# untitled.net
KiCad netlist of a schematic drawn in EAGLE
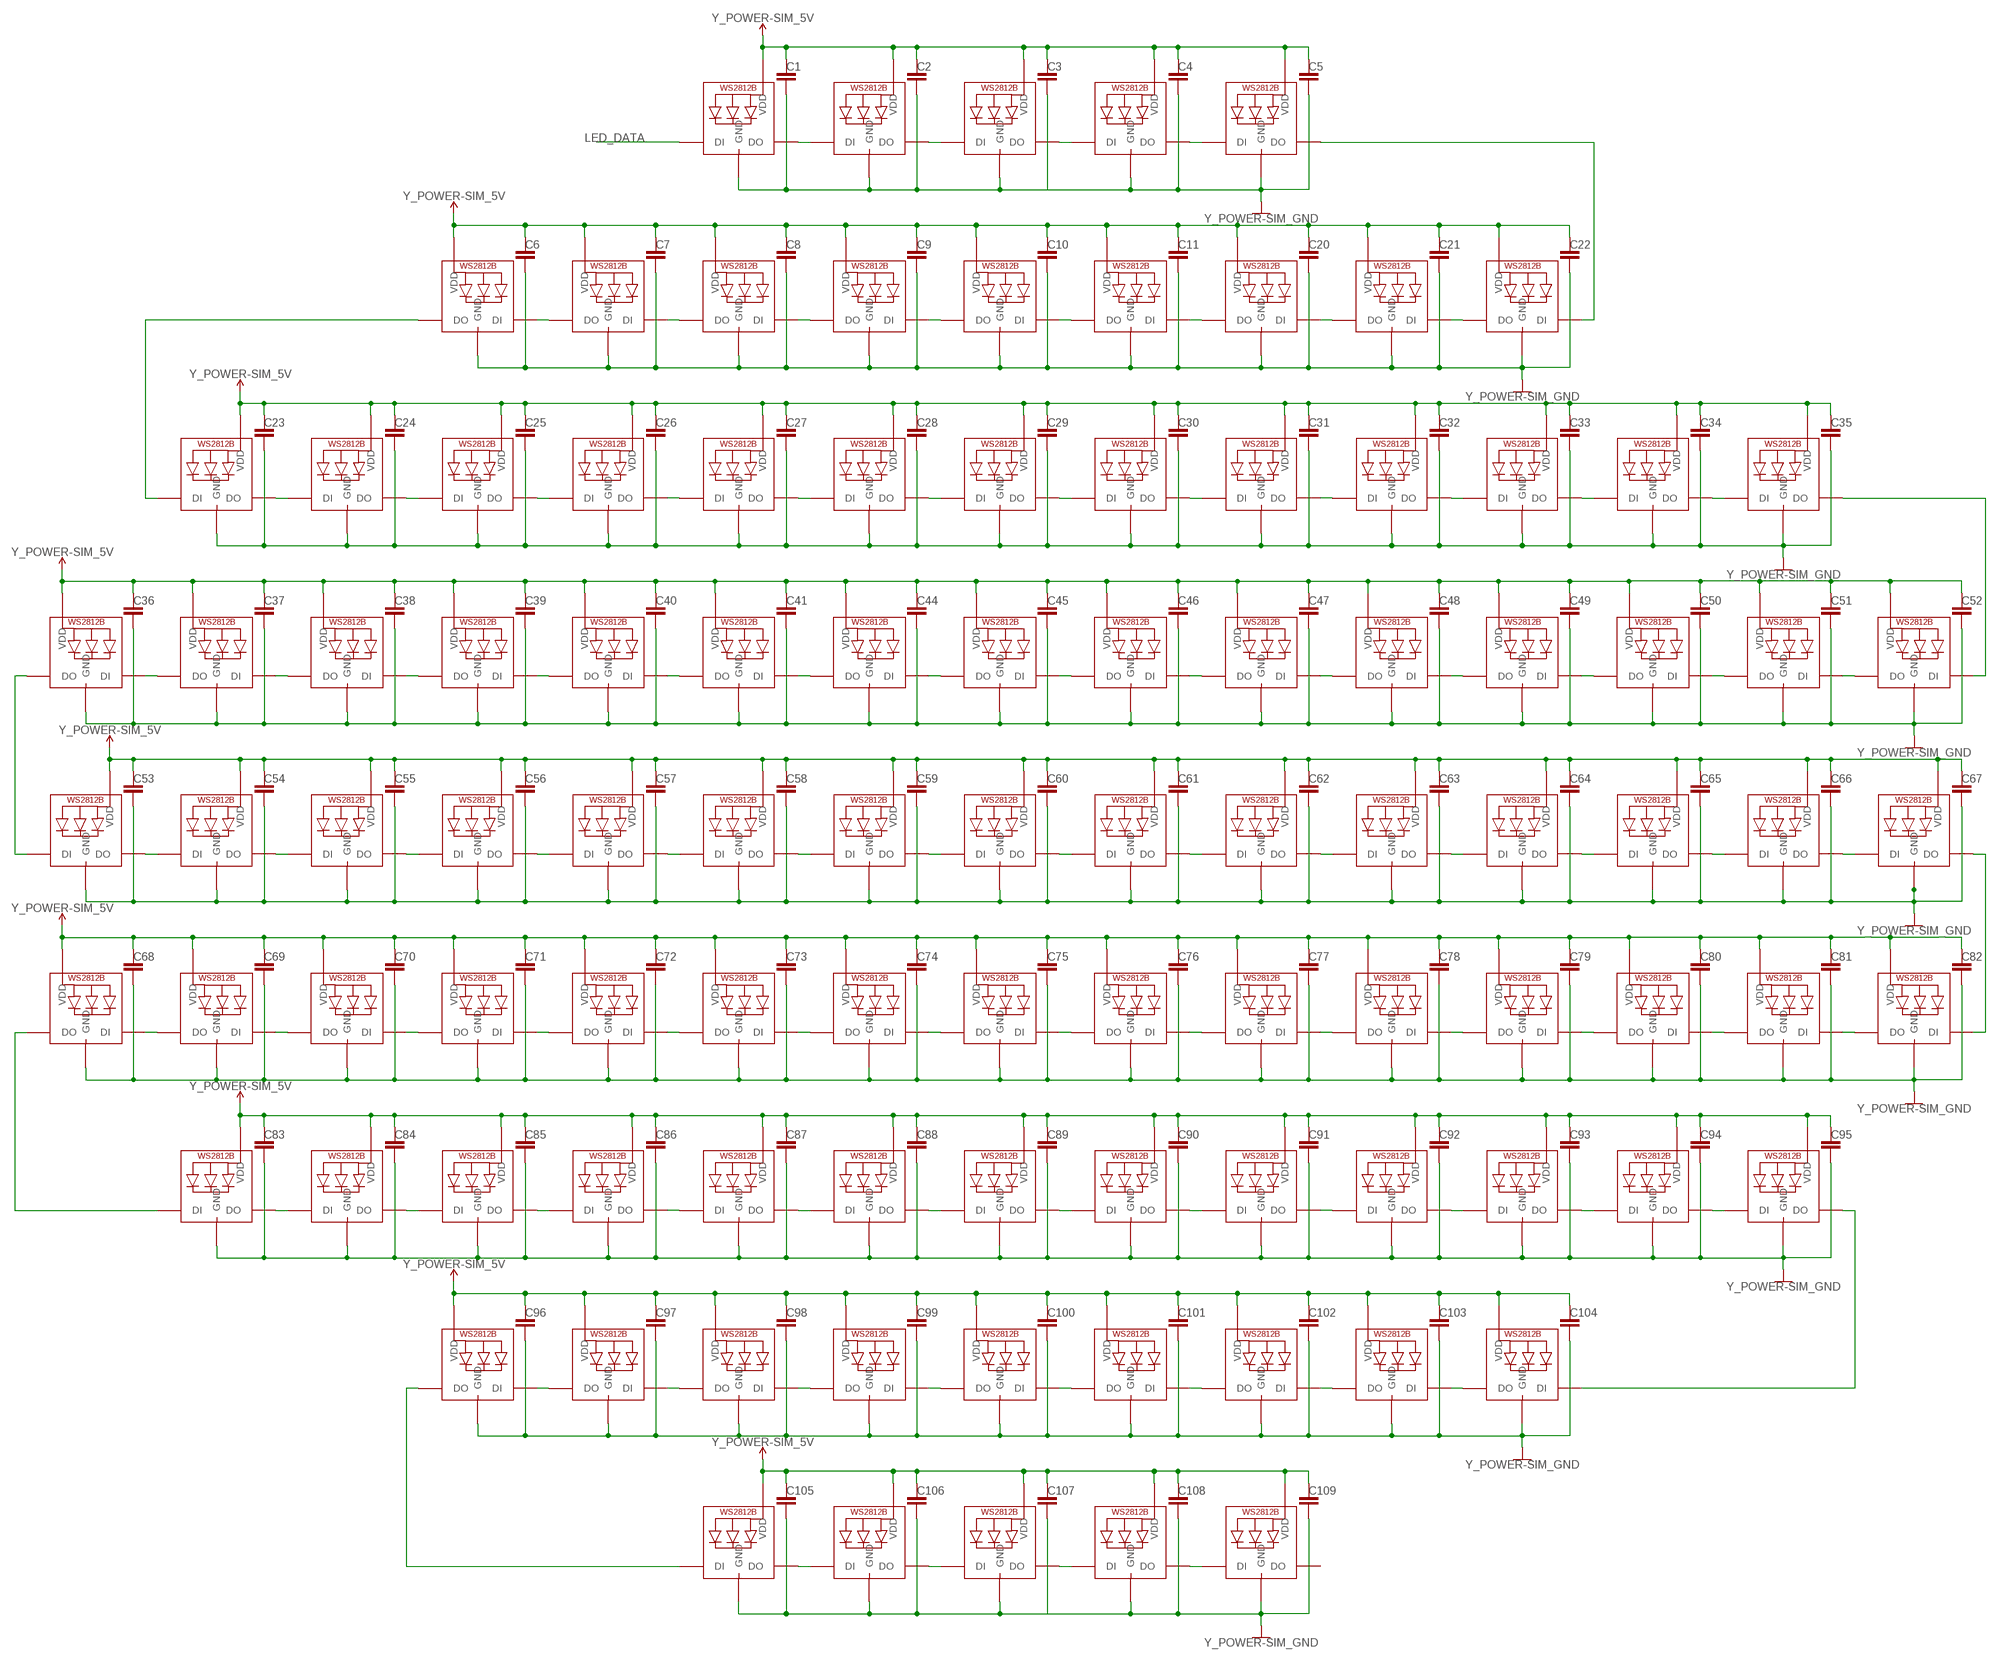
[diagram p0: schematic, sheet 1, part 1 of 2]
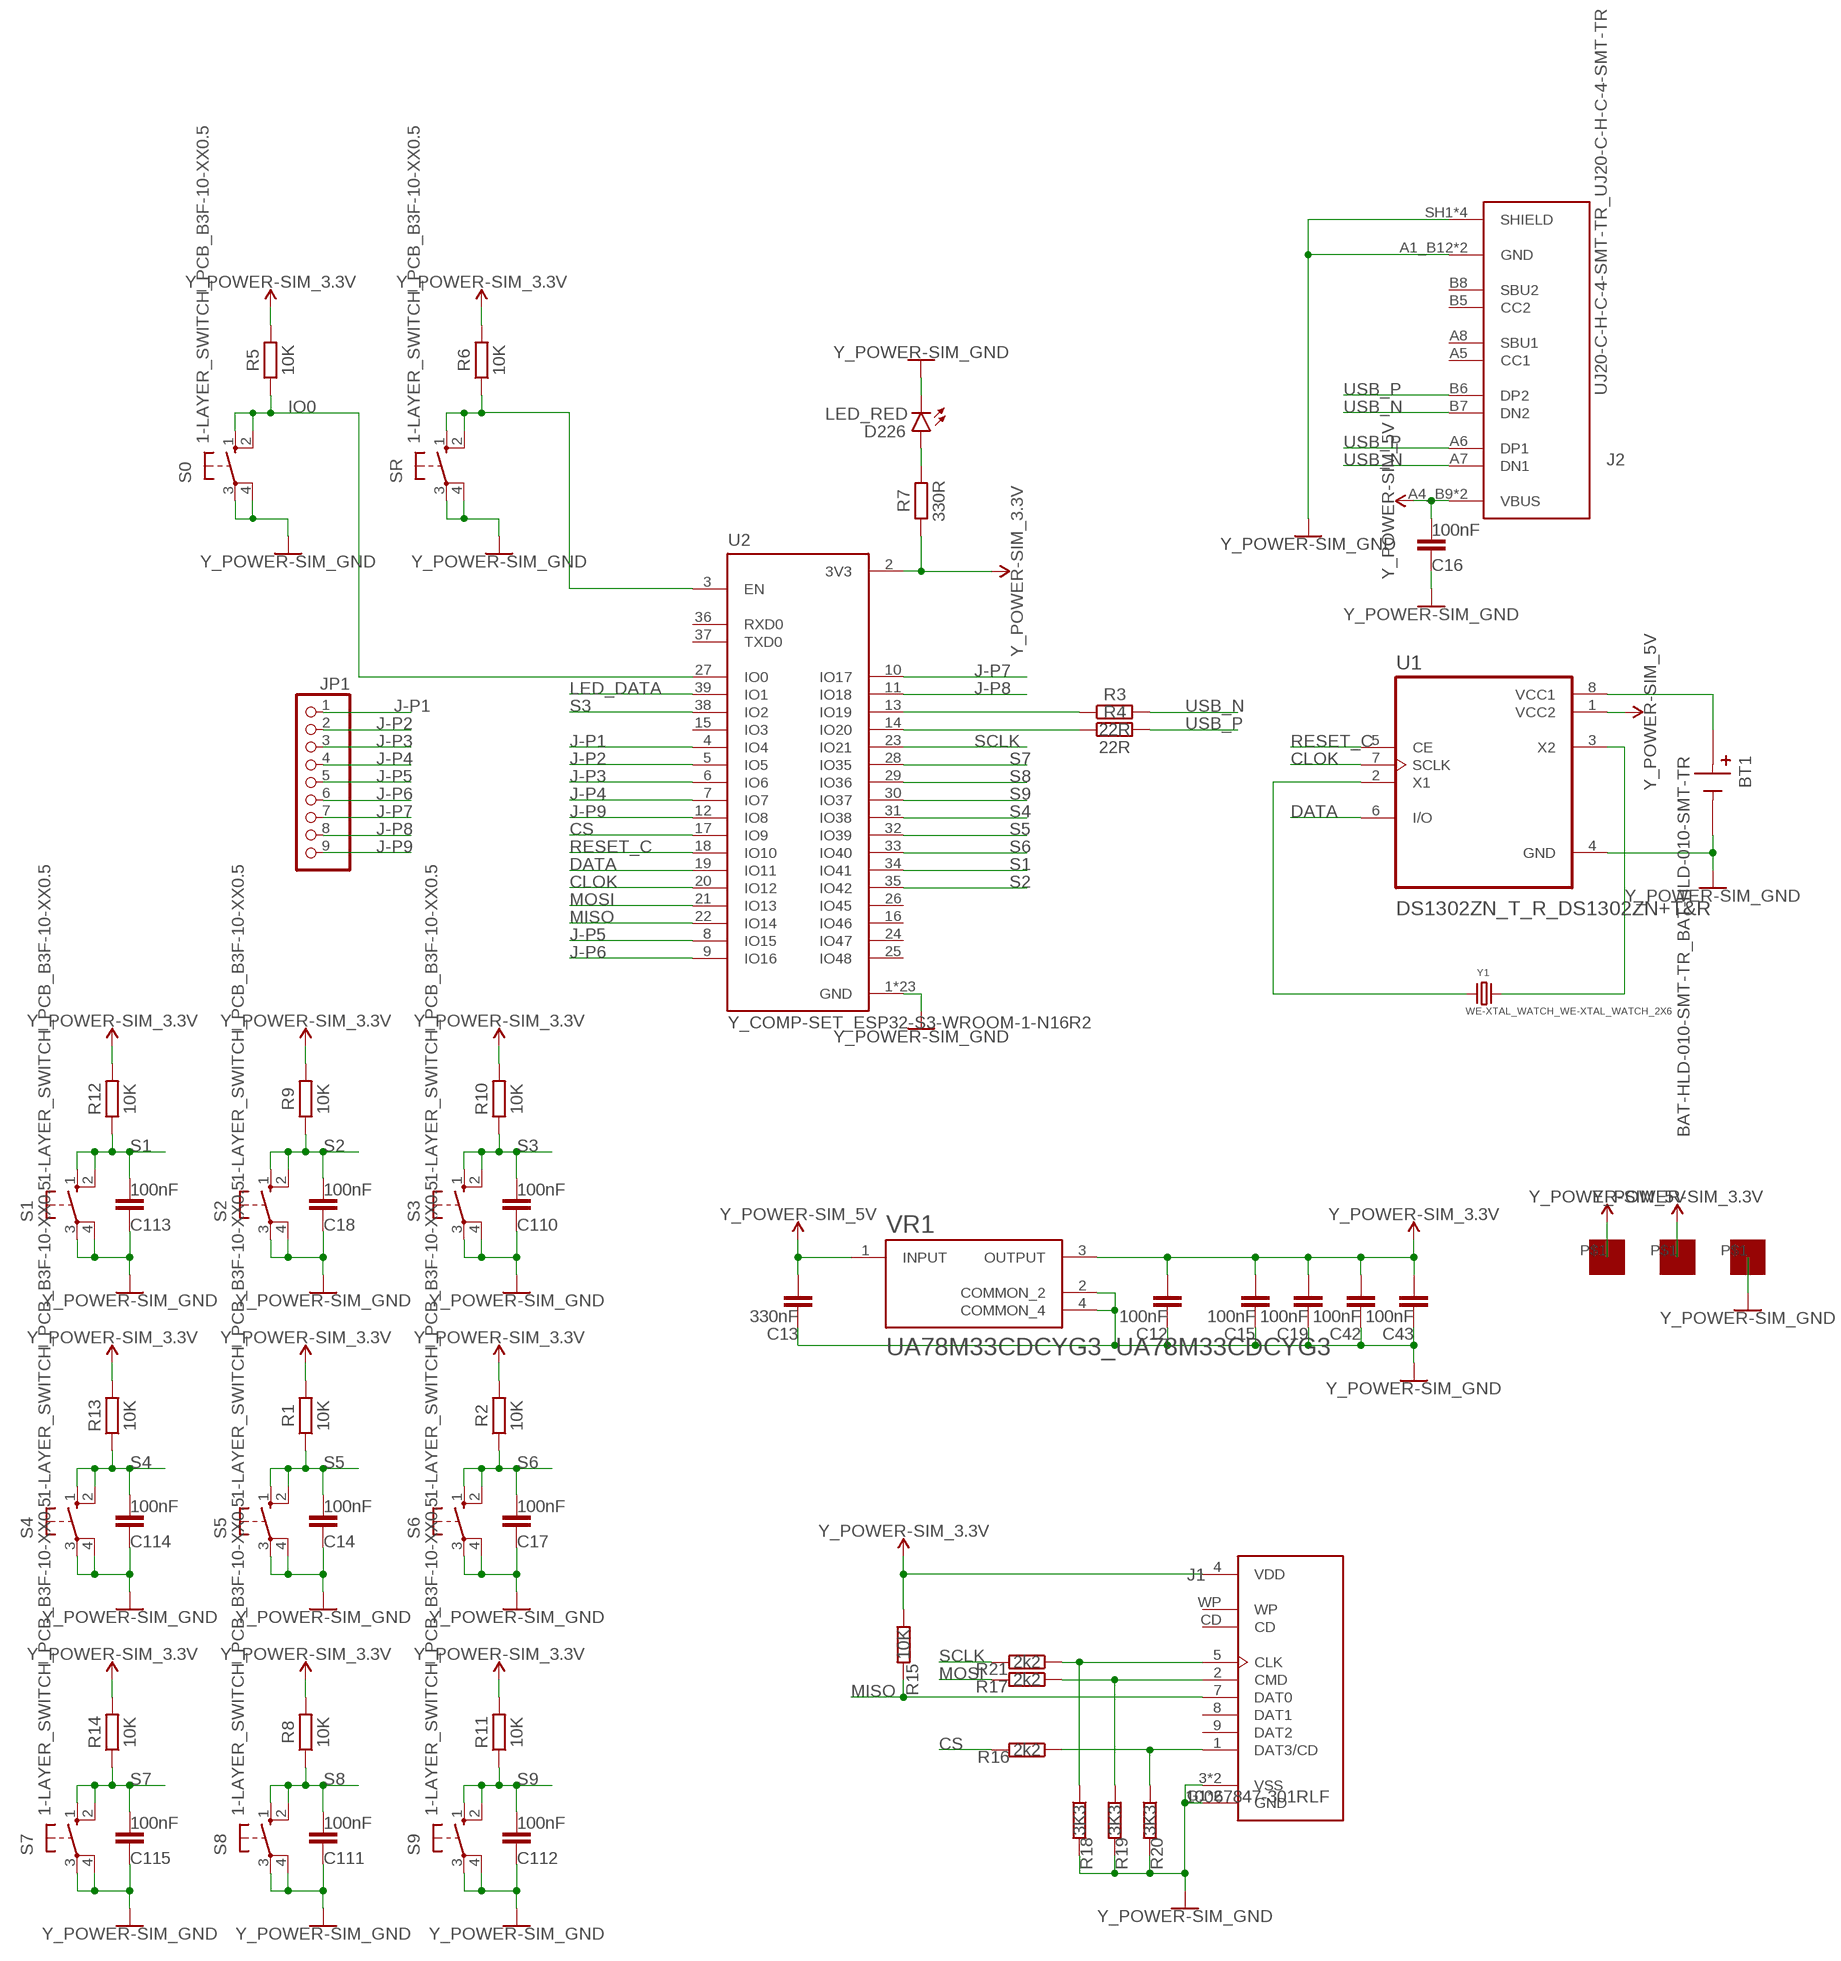
[diagram p1: schematic, sheet 1, part 2 of 2]

(export (version "E")
  (design (tool "Eeschema 10.0.6"))
  (components
    (comp (ref "BT1")
      (value "BAT-HLD-010-SMT-TR_BAT-HLD-010-SMT-TR")
      (footprint "eagle-import:BAT-HLD-010-SMT-TR_BAT_BAT-HLD-010-SMT-TR")
      (fields (field (name "MF") "TE Connectivity") (field (name "MP") "BAT-HLD-010-SMT-TR"))
      (libsource (lib "eagle-import") (part "BAT-HLD-010-SMT-TR_BAT-HLD-010-SMT-TR"))
    )
    (comp (ref "C1")
      (value "Y-CAP_C_CHIP-0805(2012-METRIC)")
      (footprint "eagle-import:Y-CAP_CAPC2012X110")
      (libsource (lib "eagle-import") (part "Y-CAP_CCHIP-0805(2012-METRIC)_"))
    )
    (comp (ref "C2")
      (value "Y-CAP_C_CHIP-0805(2012-METRIC)")
      (footprint "eagle-import:Y-CAP_CAPC2012X110")
      (libsource (lib "eagle-import") (part "Y-CAP_CCHIP-0805(2012-METRIC)_"))
    )
    (comp (ref "C3")
      (value "Y-CAP_C_CHIP-0805(2012-METRIC)")
      (footprint "eagle-import:Y-CAP_CAPC2012X110")
      (libsource (lib "eagle-import") (part "Y-CAP_CCHIP-0805(2012-METRIC)_"))
    )
    (comp (ref "C4")
      (value "Y-CAP_C_CHIP-0805(2012-METRIC)")
      (footprint "eagle-import:Y-CAP_CAPC2012X110")
      (libsource (lib "eagle-import") (part "Y-CAP_CCHIP-0805(2012-METRIC)_"))
    )
    (comp (ref "C5")
      (value "Y-CAP_C_CHIP-0805(2012-METRIC)")
      (footprint "eagle-import:Y-CAP_CAPC2012X110")
      (libsource (lib "eagle-import") (part "Y-CAP_CCHIP-0805(2012-METRIC)_"))
    )
    (comp (ref "C6")
      (value "Y-CAP_C_CHIP-0805(2012-METRIC)")
      (footprint "eagle-import:Y-CAP_CAPC2012X110")
      (libsource (lib "eagle-import") (part "Y-CAP_CCHIP-0805(2012-METRIC)_"))
    )
    (comp (ref "C7")
      (value "Y-CAP_C_CHIP-0805(2012-METRIC)")
      (footprint "eagle-import:Y-CAP_CAPC2012X110")
      (libsource (lib "eagle-import") (part "Y-CAP_CCHIP-0805(2012-METRIC)_"))
    )
    (comp (ref "C8")
      (value "Y-CAP_C_CHIP-0805(2012-METRIC)")
      (footprint "eagle-import:Y-CAP_CAPC2012X110")
      (libsource (lib "eagle-import") (part "Y-CAP_CCHIP-0805(2012-METRIC)_"))
    )
    (comp (ref "C9")
      (value "Y-CAP_C_CHIP-0805(2012-METRIC)")
      (footprint "eagle-import:Y-CAP_CAPC2012X110")
      (libsource (lib "eagle-import") (part "Y-CAP_CCHIP-0805(2012-METRIC)_"))
    )
    (comp (ref "C10")
      (value "Y-CAP_C_CHIP-0805(2012-METRIC)")
      (footprint "eagle-import:Y-CAP_CAPC2012X110")
      (libsource (lib "eagle-import") (part "Y-CAP_CCHIP-0805(2012-METRIC)_"))
    )
    (comp (ref "C11")
      (value "Y-CAP_C_CHIP-0805(2012-METRIC)")
      (footprint "eagle-import:Y-CAP_CAPC2012X110")
      (libsource (lib "eagle-import") (part "Y-CAP_CCHIP-0805(2012-METRIC)_"))
    )
    (comp (ref "C12")
      (value "100nF")
      (footprint "eagle-import:Y-CAP_CAPC2012X110")
      (libsource (lib "eagle-import") (part "Y-CAP_CCHIP-0805(2012-METRIC)_"))
    )
    (comp (ref "C13")
      (value "330nF")
      (footprint "eagle-import:Y-CAP_CAPC2012X110")
      (libsource (lib "eagle-import") (part "Y-CAP_CCHIP-0805(2012-METRIC)_"))
    )
    (comp (ref "C14")
      (value "100nF")
      (footprint "eagle-import:Y-CAP_CAPC2012X110")
      (libsource (lib "eagle-import") (part "Y-CAP_CCHIP-0805(2012-METRIC)_"))
    )
    (comp (ref "C15")
      (value "100nF")
      (footprint "eagle-import:Y-CAP_CAPC2012X110")
      (libsource (lib "eagle-import") (part "Y-CAP_CCHIP-0805(2012-METRIC)_"))
    )
    (comp (ref "C16")
      (value "100nF")
      (footprint "eagle-import:Y-CAP_CAPC2012X110")
      (libsource (lib "eagle-import") (part "Y-CAP_CCHIP-0805(2012-METRIC)_"))
    )
    (comp (ref "C17")
      (value "100nF")
      (footprint "eagle-import:Y-CAP_CAPC2012X110")
      (libsource (lib "eagle-import") (part "Y-CAP_CCHIP-0805(2012-METRIC)_"))
    )
    (comp (ref "C18")
      (value "100nF")
      (footprint "eagle-import:Y-CAP_CAPC2012X110")
      (libsource (lib "eagle-import") (part "Y-CAP_CCHIP-0805(2012-METRIC)_"))
    )
    (comp (ref "C19")
      (value "100nF")
      (footprint "eagle-import:Y-CAP_CAPC2012X110")
      (libsource (lib "eagle-import") (part "Y-CAP_CCHIP-0805(2012-METRIC)_"))
    )
    (comp (ref "C20")
      (value "Y-CAP_C_CHIP-0805(2012-METRIC)")
      (footprint "eagle-import:Y-CAP_CAPC2012X110")
      (libsource (lib "eagle-import") (part "Y-CAP_CCHIP-0805(2012-METRIC)_"))
    )
    (comp (ref "C21")
      (value "Y-CAP_C_CHIP-0805(2012-METRIC)")
      (footprint "eagle-import:Y-CAP_CAPC2012X110")
      (libsource (lib "eagle-import") (part "Y-CAP_CCHIP-0805(2012-METRIC)_"))
    )
    (comp (ref "C22")
      (value "Y-CAP_C_CHIP-0805(2012-METRIC)")
      (footprint "eagle-import:Y-CAP_CAPC2012X110")
      (libsource (lib "eagle-import") (part "Y-CAP_CCHIP-0805(2012-METRIC)_"))
    )
    (comp (ref "C23")
      (value "Y-CAP_C_CHIP-0805(2012-METRIC)")
      (footprint "eagle-import:Y-CAP_CAPC2012X110")
      (libsource (lib "eagle-import") (part "Y-CAP_CCHIP-0805(2012-METRIC)_"))
    )
    (comp (ref "C24")
      (value "Y-CAP_C_CHIP-0805(2012-METRIC)")
      (footprint "eagle-import:Y-CAP_CAPC2012X110")
      (libsource (lib "eagle-import") (part "Y-CAP_CCHIP-0805(2012-METRIC)_"))
    )
    (comp (ref "C25")
      (value "Y-CAP_C_CHIP-0805(2012-METRIC)")
      (footprint "eagle-import:Y-CAP_CAPC2012X110")
      (libsource (lib "eagle-import") (part "Y-CAP_CCHIP-0805(2012-METRIC)_"))
    )
    (comp (ref "C26")
      (value "Y-CAP_C_CHIP-0805(2012-METRIC)")
      (footprint "eagle-import:Y-CAP_CAPC2012X110")
      (libsource (lib "eagle-import") (part "Y-CAP_CCHIP-0805(2012-METRIC)_"))
    )
    (comp (ref "C27")
      (value "Y-CAP_C_CHIP-0805(2012-METRIC)")
      (footprint "eagle-import:Y-CAP_CAPC2012X110")
      (libsource (lib "eagle-import") (part "Y-CAP_CCHIP-0805(2012-METRIC)_"))
    )
    (comp (ref "C28")
      (value "Y-CAP_C_CHIP-0805(2012-METRIC)")
      (footprint "eagle-import:Y-CAP_CAPC2012X110")
      (libsource (lib "eagle-import") (part "Y-CAP_CCHIP-0805(2012-METRIC)_"))
    )
    (comp (ref "C29")
      (value "Y-CAP_C_CHIP-0805(2012-METRIC)")
      (footprint "eagle-import:Y-CAP_CAPC2012X110")
      (libsource (lib "eagle-import") (part "Y-CAP_CCHIP-0805(2012-METRIC)_"))
    )
    (comp (ref "C30")
      (value "Y-CAP_C_CHIP-0805(2012-METRIC)")
      (footprint "eagle-import:Y-CAP_CAPC2012X110")
      (libsource (lib "eagle-import") (part "Y-CAP_CCHIP-0805(2012-METRIC)_"))
    )
    (comp (ref "C31")
      (value "Y-CAP_C_CHIP-0805(2012-METRIC)")
      (footprint "eagle-import:Y-CAP_CAPC2012X110")
      (libsource (lib "eagle-import") (part "Y-CAP_CCHIP-0805(2012-METRIC)_"))
    )
    (comp (ref "C32")
      (value "Y-CAP_C_CHIP-0805(2012-METRIC)")
      (footprint "eagle-import:Y-CAP_CAPC2012X110")
      (libsource (lib "eagle-import") (part "Y-CAP_CCHIP-0805(2012-METRIC)_"))
    )
    (comp (ref "C33")
      (value "Y-CAP_C_CHIP-0805(2012-METRIC)")
      (footprint "eagle-import:Y-CAP_CAPC2012X110")
      (libsource (lib "eagle-import") (part "Y-CAP_CCHIP-0805(2012-METRIC)_"))
    )
    (comp (ref "C34")
      (value "Y-CAP_C_CHIP-0805(2012-METRIC)")
      (footprint "eagle-import:Y-CAP_CAPC2012X110")
      (libsource (lib "eagle-import") (part "Y-CAP_CCHIP-0805(2012-METRIC)_"))
    )
    (comp (ref "C35")
      (value "Y-CAP_C_CHIP-0805(2012-METRIC)")
      (footprint "eagle-import:Y-CAP_CAPC2012X110")
      (libsource (lib "eagle-import") (part "Y-CAP_CCHIP-0805(2012-METRIC)_"))
    )
    (comp (ref "C36")
      (value "Y-CAP_C_CHIP-0805(2012-METRIC)")
      (footprint "eagle-import:Y-CAP_CAPC2012X110")
      (libsource (lib "eagle-import") (part "Y-CAP_CCHIP-0805(2012-METRIC)_"))
    )
    (comp (ref "C37")
      (value "Y-CAP_C_CHIP-0805(2012-METRIC)")
      (footprint "eagle-import:Y-CAP_CAPC2012X110")
      (libsource (lib "eagle-import") (part "Y-CAP_CCHIP-0805(2012-METRIC)_"))
    )
    (comp (ref "C38")
      (value "Y-CAP_C_CHIP-0805(2012-METRIC)")
      (footprint "eagle-import:Y-CAP_CAPC2012X110")
      (libsource (lib "eagle-import") (part "Y-CAP_CCHIP-0805(2012-METRIC)_"))
    )
    (comp (ref "C39")
      (value "Y-CAP_C_CHIP-0805(2012-METRIC)")
      (footprint "eagle-import:Y-CAP_CAPC2012X110")
      (libsource (lib "eagle-import") (part "Y-CAP_CCHIP-0805(2012-METRIC)_"))
    )
    (comp (ref "C40")
      (value "Y-CAP_C_CHIP-0805(2012-METRIC)")
      (footprint "eagle-import:Y-CAP_CAPC2012X110")
      (libsource (lib "eagle-import") (part "Y-CAP_CCHIP-0805(2012-METRIC)_"))
    )
    (comp (ref "C41")
      (value "Y-CAP_C_CHIP-0805(2012-METRIC)")
      (footprint "eagle-import:Y-CAP_CAPC2012X110")
      (libsource (lib "eagle-import") (part "Y-CAP_CCHIP-0805(2012-METRIC)_"))
    )
    (comp (ref "C42")
      (value "100nF")
      (footprint "eagle-import:Y-CAP_CAPC2012X110")
      (libsource (lib "eagle-import") (part "Y-CAP_CCHIP-0805(2012-METRIC)_"))
    )
    (comp (ref "C43")
      (value "100nF")
      (footprint "eagle-import:Y-CAP_CAPC2012X110")
      (libsource (lib "eagle-import") (part "Y-CAP_CCHIP-0805(2012-METRIC)_"))
    )
    (comp (ref "C44")
      (value "Y-CAP_C_CHIP-0805(2012-METRIC)")
      (footprint "eagle-import:Y-CAP_CAPC2012X110")
      (libsource (lib "eagle-import") (part "Y-CAP_CCHIP-0805(2012-METRIC)_"))
    )
    (comp (ref "C45")
      (value "Y-CAP_C_CHIP-0805(2012-METRIC)")
      (footprint "eagle-import:Y-CAP_CAPC2012X110")
      (libsource (lib "eagle-import") (part "Y-CAP_CCHIP-0805(2012-METRIC)_"))
    )
    (comp (ref "C46")
      (value "Y-CAP_C_CHIP-0805(2012-METRIC)")
      (footprint "eagle-import:Y-CAP_CAPC2012X110")
      (libsource (lib "eagle-import") (part "Y-CAP_CCHIP-0805(2012-METRIC)_"))
    )
    (comp (ref "C47")
      (value "Y-CAP_C_CHIP-0805(2012-METRIC)")
      (footprint "eagle-import:Y-CAP_CAPC2012X110")
      (libsource (lib "eagle-import") (part "Y-CAP_CCHIP-0805(2012-METRIC)_"))
    )
    (comp (ref "C48")
      (value "Y-CAP_C_CHIP-0805(2012-METRIC)")
      (footprint "eagle-import:Y-CAP_CAPC2012X110")
      (libsource (lib "eagle-import") (part "Y-CAP_CCHIP-0805(2012-METRIC)_"))
    )
    (comp (ref "C49")
      (value "Y-CAP_C_CHIP-0805(2012-METRIC)")
      (footprint "eagle-import:Y-CAP_CAPC2012X110")
      (libsource (lib "eagle-import") (part "Y-CAP_CCHIP-0805(2012-METRIC)_"))
    )
    (comp (ref "C50")
      (value "Y-CAP_C_CHIP-0805(2012-METRIC)")
      (footprint "eagle-import:Y-CAP_CAPC2012X110")
      (libsource (lib "eagle-import") (part "Y-CAP_CCHIP-0805(2012-METRIC)_"))
    )
    (comp (ref "C51")
      (value "Y-CAP_C_CHIP-0805(2012-METRIC)")
      (footprint "eagle-import:Y-CAP_CAPC2012X110")
      (libsource (lib "eagle-import") (part "Y-CAP_CCHIP-0805(2012-METRIC)_"))
    )
    (comp (ref "C52")
      (value "Y-CAP_C_CHIP-0805(2012-METRIC)")
      (footprint "eagle-import:Y-CAP_CAPC2012X110")
      (libsource (lib "eagle-import") (part "Y-CAP_CCHIP-0805(2012-METRIC)_"))
    )
    (comp (ref "C53")
      (value "Y-CAP_C_CHIP-0805(2012-METRIC)")
      (footprint "eagle-import:Y-CAP_CAPC2012X110")
      (libsource (lib "eagle-import") (part "Y-CAP_CCHIP-0805(2012-METRIC)_"))
    )
    (comp (ref "C54")
      (value "Y-CAP_C_CHIP-0805(2012-METRIC)")
      (footprint "eagle-import:Y-CAP_CAPC2012X110")
      (libsource (lib "eagle-import") (part "Y-CAP_CCHIP-0805(2012-METRIC)_"))
    )
    (comp (ref "C55")
      (value "Y-CAP_C_CHIP-0805(2012-METRIC)")
      (footprint "eagle-import:Y-CAP_CAPC2012X110")
      (libsource (lib "eagle-import") (part "Y-CAP_CCHIP-0805(2012-METRIC)_"))
    )
    (comp (ref "C56")
      (value "Y-CAP_C_CHIP-0805(2012-METRIC)")
      (footprint "eagle-import:Y-CAP_CAPC2012X110")
      (libsource (lib "eagle-import") (part "Y-CAP_CCHIP-0805(2012-METRIC)_"))
    )
    (comp (ref "C57")
      (value "Y-CAP_C_CHIP-0805(2012-METRIC)")
      (footprint "eagle-import:Y-CAP_CAPC2012X110")
      (libsource (lib "eagle-import") (part "Y-CAP_CCHIP-0805(2012-METRIC)_"))
    )
    (comp (ref "C58")
      (value "Y-CAP_C_CHIP-0805(2012-METRIC)")
      (footprint "eagle-import:Y-CAP_CAPC2012X110")
      (libsource (lib "eagle-import") (part "Y-CAP_CCHIP-0805(2012-METRIC)_"))
    )
    (comp (ref "C59")
      (value "Y-CAP_C_CHIP-0805(2012-METRIC)")
      (footprint "eagle-import:Y-CAP_CAPC2012X110")
      (libsource (lib "eagle-import") (part "Y-CAP_CCHIP-0805(2012-METRIC)_"))
    )
    (comp (ref "C60")
      (value "Y-CAP_C_CHIP-0805(2012-METRIC)")
      (footprint "eagle-import:Y-CAP_CAPC2012X110")
      (libsource (lib "eagle-import") (part "Y-CAP_CCHIP-0805(2012-METRIC)_"))
    )
    (comp (ref "C61")
      (value "Y-CAP_C_CHIP-0805(2012-METRIC)")
      (footprint "eagle-import:Y-CAP_CAPC2012X110")
      (libsource (lib "eagle-import") (part "Y-CAP_CCHIP-0805(2012-METRIC)_"))
    )
    (comp (ref "C62")
      (value "Y-CAP_C_CHIP-0805(2012-METRIC)")
      (footprint "eagle-import:Y-CAP_CAPC2012X110")
      (libsource (lib "eagle-import") (part "Y-CAP_CCHIP-0805(2012-METRIC)_"))
    )
    (comp (ref "C63")
      (value "Y-CAP_C_CHIP-0805(2012-METRIC)")
      (footprint "eagle-import:Y-CAP_CAPC2012X110")
      (libsource (lib "eagle-import") (part "Y-CAP_CCHIP-0805(2012-METRIC)_"))
    )
    (comp (ref "C64")
      (value "Y-CAP_C_CHIP-0805(2012-METRIC)")
      (footprint "eagle-import:Y-CAP_CAPC2012X110")
      (libsource (lib "eagle-import") (part "Y-CAP_CCHIP-0805(2012-METRIC)_"))
    )
    (comp (ref "C65")
      (value "Y-CAP_C_CHIP-0805(2012-METRIC)")
      (footprint "eagle-import:Y-CAP_CAPC2012X110")
      (libsource (lib "eagle-import") (part "Y-CAP_CCHIP-0805(2012-METRIC)_"))
    )
    (comp (ref "C66")
      (value "Y-CAP_C_CHIP-0805(2012-METRIC)")
      (footprint "eagle-import:Y-CAP_CAPC2012X110")
      (libsource (lib "eagle-import") (part "Y-CAP_CCHIP-0805(2012-METRIC)_"))
    )
    (comp (ref "C67")
      (value "Y-CAP_C_CHIP-0805(2012-METRIC)")
      (footprint "eagle-import:Y-CAP_CAPC2012X110")
      (libsource (lib "eagle-import") (part "Y-CAP_CCHIP-0805(2012-METRIC)_"))
    )
    (comp (ref "C68")
      (value "Y-CAP_C_CHIP-0805(2012-METRIC)")
      (footprint "eagle-import:Y-CAP_CAPC2012X110")
      (libsource (lib "eagle-import") (part "Y-CAP_CCHIP-0805(2012-METRIC)_"))
    )
    (comp (ref "C69")
      (value "Y-CAP_C_CHIP-0805(2012-METRIC)")
      (footprint "eagle-import:Y-CAP_CAPC2012X110")
      (libsource (lib "eagle-import") (part "Y-CAP_CCHIP-0805(2012-METRIC)_"))
    )
    (comp (ref "C70")
      (value "Y-CAP_C_CHIP-0805(2012-METRIC)")
      (footprint "eagle-import:Y-CAP_CAPC2012X110")
      (libsource (lib "eagle-import") (part "Y-CAP_CCHIP-0805(2012-METRIC)_"))
    )
    (comp (ref "C71")
      (value "Y-CAP_C_CHIP-0805(2012-METRIC)")
      (footprint "eagle-import:Y-CAP_CAPC2012X110")
      (libsource (lib "eagle-import") (part "Y-CAP_CCHIP-0805(2012-METRIC)_"))
    )
    (comp (ref "C72")
      (value "Y-CAP_C_CHIP-0805(2012-METRIC)")
      (footprint "eagle-import:Y-CAP_CAPC2012X110")
      (libsource (lib "eagle-import") (part "Y-CAP_CCHIP-0805(2012-METRIC)_"))
    )
    (comp (ref "C73")
      (value "Y-CAP_C_CHIP-0805(2012-METRIC)")
      (footprint "eagle-import:Y-CAP_CAPC2012X110")
      (libsource (lib "eagle-import") (part "Y-CAP_CCHIP-0805(2012-METRIC)_"))
    )
    (comp (ref "C74")
      (value "Y-CAP_C_CHIP-0805(2012-METRIC)")
      (footprint "eagle-import:Y-CAP_CAPC2012X110")
      (libsource (lib "eagle-import") (part "Y-CAP_CCHIP-0805(2012-METRIC)_"))
    )
    (comp (ref "C75")
      (value "Y-CAP_C_CHIP-0805(2012-METRIC)")
      (footprint "eagle-import:Y-CAP_CAPC2012X110")
      (libsource (lib "eagle-import") (part "Y-CAP_CCHIP-0805(2012-METRIC)_"))
    )
    (comp (ref "C76")
      (value "Y-CAP_C_CHIP-0805(2012-METRIC)")
      (footprint "eagle-import:Y-CAP_CAPC2012X110")
      (libsource (lib "eagle-import") (part "Y-CAP_CCHIP-0805(2012-METRIC)_"))
    )
    (comp (ref "C77")
      (value "Y-CAP_C_CHIP-0805(2012-METRIC)")
      (footprint "eagle-import:Y-CAP_CAPC2012X110")
      (libsource (lib "eagle-import") (part "Y-CAP_CCHIP-0805(2012-METRIC)_"))
    )
    (comp (ref "C78")
      (value "Y-CAP_C_CHIP-0805(2012-METRIC)")
      (footprint "eagle-import:Y-CAP_CAPC2012X110")
      (libsource (lib "eagle-import") (part "Y-CAP_CCHIP-0805(2012-METRIC)_"))
    )
    (comp (ref "C79")
      (value "Y-CAP_C_CHIP-0805(2012-METRIC)")
      (footprint "eagle-import:Y-CAP_CAPC2012X110")
      (libsource (lib "eagle-import") (part "Y-CAP_CCHIP-0805(2012-METRIC)_"))
    )
    (comp (ref "C80")
      (value "Y-CAP_C_CHIP-0805(2012-METRIC)")
      (footprint "eagle-import:Y-CAP_CAPC2012X110")
      (libsource (lib "eagle-import") (part "Y-CAP_CCHIP-0805(2012-METRIC)_"))
    )
    (comp (ref "C81")
      (value "Y-CAP_C_CHIP-0805(2012-METRIC)")
      (footprint "eagle-import:Y-CAP_CAPC2012X110")
      (libsource (lib "eagle-import") (part "Y-CAP_CCHIP-0805(2012-METRIC)_"))
    )
    (comp (ref "C82")
      (value "Y-CAP_C_CHIP-0805(2012-METRIC)")
      (footprint "eagle-import:Y-CAP_CAPC2012X110")
      (libsource (lib "eagle-import") (part "Y-CAP_CCHIP-0805(2012-METRIC)_"))
    )
    (comp (ref "C83")
      (value "Y-CAP_C_CHIP-0805(2012-METRIC)")
      (footprint "eagle-import:Y-CAP_CAPC2012X110")
      (libsource (lib "eagle-import") (part "Y-CAP_CCHIP-0805(2012-METRIC)_"))
    )
    (comp (ref "C84")
      (value "Y-CAP_C_CHIP-0805(2012-METRIC)")
      (footprint "eagle-import:Y-CAP_CAPC2012X110")
      (libsource (lib "eagle-import") (part "Y-CAP_CCHIP-0805(2012-METRIC)_"))
    )
    (comp (ref "C85")
      (value "Y-CAP_C_CHIP-0805(2012-METRIC)")
      (footprint "eagle-import:Y-CAP_CAPC2012X110")
      (libsource (lib "eagle-import") (part "Y-CAP_CCHIP-0805(2012-METRIC)_"))
    )
    (comp (ref "C86")
      (value "Y-CAP_C_CHIP-0805(2012-METRIC)")
      (footprint "eagle-import:Y-CAP_CAPC2012X110")
      (libsource (lib "eagle-import") (part "Y-CAP_CCHIP-0805(2012-METRIC)_"))
    )
    (comp (ref "C87")
      (value "Y-CAP_C_CHIP-0805(2012-METRIC)")
      (footprint "eagle-import:Y-CAP_CAPC2012X110")
      (libsource (lib "eagle-import") (part "Y-CAP_CCHIP-0805(2012-METRIC)_"))
    )
    (comp (ref "C88")
      (value "Y-CAP_C_CHIP-0805(2012-METRIC)")
      (footprint "eagle-import:Y-CAP_CAPC2012X110")
      (libsource (lib "eagle-import") (part "Y-CAP_CCHIP-0805(2012-METRIC)_"))
    )
    (comp (ref "C89")
      (value "Y-CAP_C_CHIP-0805(2012-METRIC)")
      (footprint "eagle-import:Y-CAP_CAPC2012X110")
      (libsource (lib "eagle-import") (part "Y-CAP_CCHIP-0805(2012-METRIC)_"))
    )
    (comp (ref "C90")
      (value "Y-CAP_C_CHIP-0805(2012-METRIC)")
      (footprint "eagle-import:Y-CAP_CAPC2012X110")
      (libsource (lib "eagle-import") (part "Y-CAP_CCHIP-0805(2012-METRIC)_"))
    )
    (comp (ref "C91")
      (value "Y-CAP_C_CHIP-0805(2012-METRIC)")
      (footprint "eagle-import:Y-CAP_CAPC2012X110")
      (libsource (lib "eagle-import") (part "Y-CAP_CCHIP-0805(2012-METRIC)_"))
    )
    (comp (ref "C92")
      (value "Y-CAP_C_CHIP-0805(2012-METRIC)")
      (footprint "eagle-import:Y-CAP_CAPC2012X110")
      (libsource (lib "eagle-import") (part "Y-CAP_CCHIP-0805(2012-METRIC)_"))
    )
    (comp (ref "C93")
      (value "Y-CAP_C_CHIP-0805(2012-METRIC)")
      (footprint "eagle-import:Y-CAP_CAPC2012X110")
      (libsource (lib "eagle-import") (part "Y-CAP_CCHIP-0805(2012-METRIC)_"))
    )
    (comp (ref "C94")
      (value "Y-CAP_C_CHIP-0805(2012-METRIC)")
      (footprint "eagle-import:Y-CAP_CAPC2012X110")
      (libsource (lib "eagle-import") (part "Y-CAP_CCHIP-0805(2012-METRIC)_"))
    )
    (comp (ref "C95")
      (value "Y-CAP_C_CHIP-0805(2012-METRIC)")
      (footprint "eagle-import:Y-CAP_CAPC2012X110")
      (libsource (lib "eagle-import") (part "Y-CAP_CCHIP-0805(2012-METRIC)_"))
    )
    (comp (ref "C96")
      (value "Y-CAP_C_CHIP-0805(2012-METRIC)")
      (footprint "eagle-import:Y-CAP_CAPC2012X110")
      (libsource (lib "eagle-import") (part "Y-CAP_CCHIP-0805(2012-METRIC)_"))
    )
    (comp (ref "C97")
      (value "Y-CAP_C_CHIP-0805(2012-METRIC)")
      (footprint "eagle-import:Y-CAP_CAPC2012X110")
      (libsource (lib "eagle-import") (part "Y-CAP_CCHIP-0805(2012-METRIC)_"))
    )
    (comp (ref "C98")
      (value "Y-CAP_C_CHIP-0805(2012-METRIC)")
      (footprint "eagle-import:Y-CAP_CAPC2012X110")
      (libsource (lib "eagle-import") (part "Y-CAP_CCHIP-0805(2012-METRIC)_"))
    )
    (comp (ref "C99")
      (value "Y-CAP_C_CHIP-0805(2012-METRIC)")
      (footprint "eagle-import:Y-CAP_CAPC2012X110")
      (libsource (lib "eagle-import") (part "Y-CAP_CCHIP-0805(2012-METRIC)_"))
    )
    (comp (ref "C100")
      (value "Y-CAP_C_CHIP-0805(2012-METRIC)")
      (footprint "eagle-import:Y-CAP_CAPC2012X110")
      (libsource (lib "eagle-import") (part "Y-CAP_CCHIP-0805(2012-METRIC)_"))
    )
    (comp (ref "C101")
      (value "Y-CAP_C_CHIP-0805(2012-METRIC)")
      (footprint "eagle-import:Y-CAP_CAPC2012X110")
      (libsource (lib "eagle-import") (part "Y-CAP_CCHIP-0805(2012-METRIC)_"))
    )
    (comp (ref "C102")
      (value "Y-CAP_C_CHIP-0805(2012-METRIC)")
      (footprint "eagle-import:Y-CAP_CAPC2012X110")
      (libsource (lib "eagle-import") (part "Y-CAP_CCHIP-0805(2012-METRIC)_"))
    )
    (comp (ref "C103")
      (value "Y-CAP_C_CHIP-0805(2012-METRIC)")
      (footprint "eagle-import:Y-CAP_CAPC2012X110")
      (libsource (lib "eagle-import") (part "Y-CAP_CCHIP-0805(2012-METRIC)_"))
    )
    (comp (ref "C104")
      (value "Y-CAP_C_CHIP-0805(2012-METRIC)")
      (footprint "eagle-import:Y-CAP_CAPC2012X110")
      (libsource (lib "eagle-import") (part "Y-CAP_CCHIP-0805(2012-METRIC)_"))
    )
    (comp (ref "C105")
      (value "Y-CAP_C_CHIP-0805(2012-METRIC)")
      (footprint "eagle-import:Y-CAP_CAPC2012X110")
      (libsource (lib "eagle-import") (part "Y-CAP_CCHIP-0805(2012-METRIC)_"))
    )
    (comp (ref "C106")
      (value "Y-CAP_C_CHIP-0805(2012-METRIC)")
      (footprint "eagle-import:Y-CAP_CAPC2012X110")
      (libsource (lib "eagle-import") (part "Y-CAP_CCHIP-0805(2012-METRIC)_"))
    )
    (comp (ref "C107")
      (value "Y-CAP_C_CHIP-0805(2012-METRIC)")
      (footprint "eagle-import:Y-CAP_CAPC2012X110")
      (libsource (lib "eagle-import") (part "Y-CAP_CCHIP-0805(2012-METRIC)_"))
    )
    (comp (ref "C108")
      (value "Y-CAP_C_CHIP-0805(2012-METRIC)")
      (footprint "eagle-import:Y-CAP_CAPC2012X110")
      (libsource (lib "eagle-import") (part "Y-CAP_CCHIP-0805(2012-METRIC)_"))
    )
    (comp (ref "C109")
      (value "Y-CAP_C_CHIP-0805(2012-METRIC)")
      (footprint "eagle-import:Y-CAP_CAPC2012X110")
      (libsource (lib "eagle-import") (part "Y-CAP_CCHIP-0805(2012-METRIC)_"))
    )
    (comp (ref "C110")
      (value "100nF")
      (footprint "eagle-import:Y-CAP_CAPC2012X110")
      (libsource (lib "eagle-import") (part "Y-CAP_CCHIP-0805(2012-METRIC)_"))
    )
    (comp (ref "C111")
      (value "100nF")
      (footprint "eagle-import:Y-CAP_CAPC2012X110")
      (libsource (lib "eagle-import") (part "Y-CAP_CCHIP-0805(2012-METRIC)_"))
    )
    (comp (ref "C112")
      (value "100nF")
      (footprint "eagle-import:Y-CAP_CAPC2012X110")
      (libsource (lib "eagle-import") (part "Y-CAP_CCHIP-0805(2012-METRIC)_"))
    )
    (comp (ref "C113")
      (value "100nF")
      (footprint "eagle-import:Y-CAP_CAPC2012X110")
      (libsource (lib "eagle-import") (part "Y-CAP_CCHIP-0805(2012-METRIC)_"))
    )
    (comp (ref "C114")
      (value "100nF")
      (footprint "eagle-import:Y-CAP_CAPC2012X110")
      (libsource (lib "eagle-import") (part "Y-CAP_CCHIP-0805(2012-METRIC)_"))
    )
    (comp (ref "C115")
      (value "100nF")
      (footprint "eagle-import:Y-CAP_CAPC2012X110")
      (libsource (lib "eagle-import") (part "Y-CAP_CCHIP-0805(2012-METRIC)_"))
    )
    (comp (ref "D226")
      (value "LED_RED")
      (footprint "eagle-import:1-LAYER_LED5MM_R-ROC")
      (libsource (lib "eagle-import") (part "1-LAYER_LED/R/5MM0.5_"))
    )
    (comp (ref "J1")
      (value "10067847-301RLF")
      (footprint "eagle-import:AMPHENOL_10067847-301RLF")
      (fields (field (name "MF") "AMPHENOL ICC / FCI"))
      (libsource (lib "eagle-import") (part "10067847-301RLF"))
    )
    (comp (ref "J2")
      (value "UJ20-C-H-C-4-SMT-TR_UJ20-C-H-C-4-SMT-TR")
      (footprint "eagle-import:UJ20-C-H-C-4-SMT-TR_CUI_UJ20-C-H-C-4-SMT-TR")
      (fields (field (name "MF") "Same Sky") (field (name "MP") "UJ20-C-H-C-4-SMT-TR"))
      (libsource (lib "eagle-import") (part "UJ20-C-H-C-4-SMT-TR_UJ20-C-H-C-4-SMT-TR"))
    )
    (comp (ref "JP1")
      (value "1-LAYER_PINHD-1X9")
      (footprint "eagle-import:1-LAYER_1X09")
      (libsource (lib "eagle-import") (part "1-LAYER_PINHD-1X9"))
    )
    (comp (ref "LED1")
      (value "WS2812B_WS2812B_5050N")
      (footprint "eagle-import:WS2812B_WS2812B-NARROW")
      (fields (field (name "MF") "Worldsemi") (field (name "MP") "WS2812B"))
      (libsource (lib "eagle-import") (part "WS2812B_WS2812B_5050N"))
    )
    (comp (ref "LED2")
      (value "WS2812B_WS2812B_5050N")
      (footprint "eagle-import:WS2812B_WS2812B-NARROW")
      (fields (field (name "MF") "Worldsemi") (field (name "MP") "WS2812B"))
      (libsource (lib "eagle-import") (part "WS2812B_WS2812B_5050N"))
    )
    (comp (ref "LED3")
      (value "WS2812B_WS2812B_5050N")
      (footprint "eagle-import:WS2812B_WS2812B-NARROW")
      (fields (field (name "MF") "Worldsemi") (field (name "MP") "WS2812B"))
      (libsource (lib "eagle-import") (part "WS2812B_WS2812B_5050N"))
    )
    (comp (ref "LED4")
      (value "WS2812B_WS2812B_5050N")
      (footprint "eagle-import:WS2812B_WS2812B-NARROW")
      (fields (field (name "MF") "Worldsemi") (field (name "MP") "WS2812B"))
      (libsource (lib "eagle-import") (part "WS2812B_WS2812B_5050N"))
    )
    (comp (ref "LED5")
      (value "WS2812B_WS2812B_5050N")
      (footprint "eagle-import:WS2812B_WS2812B-NARROW")
      (fields (field (name "MF") "Worldsemi") (field (name "MP") "WS2812B"))
      (libsource (lib "eagle-import") (part "WS2812B_WS2812B_5050N"))
    )
    (comp (ref "LED6")
      (value "WS2812B_WS2812B_5050N")
      (footprint "eagle-import:WS2812B_WS2812B-NARROW")
      (fields (field (name "MF") "Worldsemi") (field (name "MP") "WS2812B"))
      (libsource (lib "eagle-import") (part "WS2812B_WS2812B_5050N"))
    )
    (comp (ref "LED7")
      (value "WS2812B_WS2812B_5050N")
      (footprint "eagle-import:WS2812B_WS2812B-NARROW")
      (fields (field (name "MF") "Worldsemi") (field (name "MP") "WS2812B"))
      (libsource (lib "eagle-import") (part "WS2812B_WS2812B_5050N"))
    )
    (comp (ref "LED8")
      (value "WS2812B_WS2812B_5050N")
      (footprint "eagle-import:WS2812B_WS2812B-NARROW")
      (fields (field (name "MF") "Worldsemi") (field (name "MP") "WS2812B"))
      (libsource (lib "eagle-import") (part "WS2812B_WS2812B_5050N"))
    )
    (comp (ref "LED9")
      (value "WS2812B_WS2812B_5050N")
      (footprint "eagle-import:WS2812B_WS2812B-NARROW")
      (fields (field (name "MF") "Worldsemi") (field (name "MP") "WS2812B"))
      (libsource (lib "eagle-import") (part "WS2812B_WS2812B_5050N"))
    )
    (comp (ref "LED10")
      (value "WS2812B_WS2812B_5050N")
      (footprint "eagle-import:WS2812B_WS2812B-NARROW")
      (fields (field (name "MF") "Worldsemi") (field (name "MP") "WS2812B"))
      (libsource (lib "eagle-import") (part "WS2812B_WS2812B_5050N"))
    )
    (comp (ref "LED11")
      (value "WS2812B_WS2812B_5050N")
      (footprint "eagle-import:WS2812B_WS2812B-NARROW")
      (fields (field (name "MF") "Worldsemi") (field (name "MP") "WS2812B"))
      (libsource (lib "eagle-import") (part "WS2812B_WS2812B_5050N"))
    )
    (comp (ref "LED12")
      (value "WS2812B_WS2812B_5050N")
      (footprint "eagle-import:WS2812B_WS2812B-NARROW")
      (fields (field (name "MF") "Worldsemi") (field (name "MP") "WS2812B"))
      (libsource (lib "eagle-import") (part "WS2812B_WS2812B_5050N"))
    )
    (comp (ref "LED13")
      (value "WS2812B_WS2812B_5050N")
      (footprint "eagle-import:WS2812B_WS2812B-NARROW")
      (fields (field (name "MF") "Worldsemi") (field (name "MP") "WS2812B"))
      (libsource (lib "eagle-import") (part "WS2812B_WS2812B_5050N"))
    )
    (comp (ref "LED14")
      (value "WS2812B_WS2812B_5050N")
      (footprint "eagle-import:WS2812B_WS2812B-NARROW")
      (fields (field (name "MF") "Worldsemi") (field (name "MP") "WS2812B"))
      (libsource (lib "eagle-import") (part "WS2812B_WS2812B_5050N"))
    )
    (comp (ref "LED15")
      (value "WS2812B_WS2812B_5050N")
      (footprint "eagle-import:WS2812B_WS2812B-NARROW")
      (fields (field (name "MF") "Worldsemi") (field (name "MP") "WS2812B"))
      (libsource (lib "eagle-import") (part "WS2812B_WS2812B_5050N"))
    )
    (comp (ref "LED16")
      (value "WS2812B_WS2812B_5050N")
      (footprint "eagle-import:WS2812B_WS2812B-NARROW")
      (fields (field (name "MF") "Worldsemi") (field (name "MP") "WS2812B"))
      (libsource (lib "eagle-import") (part "WS2812B_WS2812B_5050N"))
    )
    (comp (ref "LED17")
      (value "WS2812B_WS2812B_5050N")
      (footprint "eagle-import:WS2812B_WS2812B-NARROW")
      (fields (field (name "MF") "Worldsemi") (field (name "MP") "WS2812B"))
      (libsource (lib "eagle-import") (part "WS2812B_WS2812B_5050N"))
    )
    (comp (ref "LED18")
      (value "WS2812B_WS2812B_5050N")
      (footprint "eagle-import:WS2812B_WS2812B-NARROW")
      (fields (field (name "MF") "Worldsemi") (field (name "MP") "WS2812B"))
      (libsource (lib "eagle-import") (part "WS2812B_WS2812B_5050N"))
    )
    (comp (ref "LED19")
      (value "WS2812B_WS2812B_5050N")
      (footprint "eagle-import:WS2812B_WS2812B-NARROW")
      (fields (field (name "MF") "Worldsemi") (field (name "MP") "WS2812B"))
      (libsource (lib "eagle-import") (part "WS2812B_WS2812B_5050N"))
    )
    (comp (ref "LED20")
      (value "WS2812B_WS2812B_5050N")
      (footprint "eagle-import:WS2812B_WS2812B-NARROW")
      (fields (field (name "MF") "Worldsemi") (field (name "MP") "WS2812B"))
      (libsource (lib "eagle-import") (part "WS2812B_WS2812B_5050N"))
    )
    (comp (ref "LED21")
      (value "WS2812B_WS2812B_5050N")
      (footprint "eagle-import:WS2812B_WS2812B-NARROW")
      (fields (field (name "MF") "Worldsemi") (field (name "MP") "WS2812B"))
      (libsource (lib "eagle-import") (part "WS2812B_WS2812B_5050N"))
    )
    (comp (ref "LED22")
      (value "WS2812B_WS2812B_5050N")
      (footprint "eagle-import:WS2812B_WS2812B-NARROW")
      (fields (field (name "MF") "Worldsemi") (field (name "MP") "WS2812B"))
      (libsource (lib "eagle-import") (part "WS2812B_WS2812B_5050N"))
    )
    (comp (ref "LED23")
      (value "WS2812B_WS2812B_5050N")
      (footprint "eagle-import:WS2812B_WS2812B-NARROW")
      (fields (field (name "MF") "Worldsemi") (field (name "MP") "WS2812B"))
      (libsource (lib "eagle-import") (part "WS2812B_WS2812B_5050N"))
    )
    (comp (ref "LED24")
      (value "WS2812B_WS2812B_5050N")
      (footprint "eagle-import:WS2812B_WS2812B-NARROW")
      (fields (field (name "MF") "Worldsemi") (field (name "MP") "WS2812B"))
      (libsource (lib "eagle-import") (part "WS2812B_WS2812B_5050N"))
    )
    (comp (ref "LED25")
      (value "WS2812B_WS2812B_5050N")
      (footprint "eagle-import:WS2812B_WS2812B-NARROW")
      (fields (field (name "MF") "Worldsemi") (field (name "MP") "WS2812B"))
      (libsource (lib "eagle-import") (part "WS2812B_WS2812B_5050N"))
    )
    (comp (ref "LED26")
      (value "WS2812B_WS2812B_5050N")
      (footprint "eagle-import:WS2812B_WS2812B-NARROW")
      (fields (field (name "MF") "Worldsemi") (field (name "MP") "WS2812B"))
      (libsource (lib "eagle-import") (part "WS2812B_WS2812B_5050N"))
    )
    (comp (ref "LED27")
      (value "WS2812B_WS2812B_5050N")
      (footprint "eagle-import:WS2812B_WS2812B-NARROW")
      (fields (field (name "MF") "Worldsemi") (field (name "MP") "WS2812B"))
      (libsource (lib "eagle-import") (part "WS2812B_WS2812B_5050N"))
    )
    (comp (ref "LED28")
      (value "WS2812B_WS2812B_5050N")
      (footprint "eagle-import:WS2812B_WS2812B-NARROW")
      (fields (field (name "MF") "Worldsemi") (field (name "MP") "WS2812B"))
      (libsource (lib "eagle-import") (part "WS2812B_WS2812B_5050N"))
    )
    (comp (ref "LED29")
      (value "WS2812B_WS2812B_5050N")
      (footprint "eagle-import:WS2812B_WS2812B-NARROW")
      (fields (field (name "MF") "Worldsemi") (field (name "MP") "WS2812B"))
      (libsource (lib "eagle-import") (part "WS2812B_WS2812B_5050N"))
    )
    (comp (ref "LED30")
      (value "WS2812B_WS2812B_5050N")
      (footprint "eagle-import:WS2812B_WS2812B-NARROW")
      (fields (field (name "MF") "Worldsemi") (field (name "MP") "WS2812B"))
      (libsource (lib "eagle-import") (part "WS2812B_WS2812B_5050N"))
    )
    (comp (ref "LED31")
      (value "WS2812B_WS2812B_5050N")
      (footprint "eagle-import:WS2812B_WS2812B-NARROW")
      (fields (field (name "MF") "Worldsemi") (field (name "MP") "WS2812B"))
      (libsource (lib "eagle-import") (part "WS2812B_WS2812B_5050N"))
    )
    (comp (ref "LED32")
      (value "WS2812B_WS2812B_5050N")
      (footprint "eagle-import:WS2812B_WS2812B-NARROW")
      (fields (field (name "MF") "Worldsemi") (field (name "MP") "WS2812B"))
      (libsource (lib "eagle-import") (part "WS2812B_WS2812B_5050N"))
    )
    (comp (ref "LED33")
      (value "WS2812B_WS2812B_5050N")
      (footprint "eagle-import:WS2812B_WS2812B-NARROW")
      (fields (field (name "MF") "Worldsemi") (field (name "MP") "WS2812B"))
      (libsource (lib "eagle-import") (part "WS2812B_WS2812B_5050N"))
    )
    (comp (ref "LED34")
      (value "WS2812B_WS2812B_5050N")
      (footprint "eagle-import:WS2812B_WS2812B-NARROW")
      (fields (field (name "MF") "Worldsemi") (field (name "MP") "WS2812B"))
      (libsource (lib "eagle-import") (part "WS2812B_WS2812B_5050N"))
    )
    (comp (ref "LED35")
      (value "WS2812B_WS2812B_5050N")
      (footprint "eagle-import:WS2812B_WS2812B-NARROW")
      (fields (field (name "MF") "Worldsemi") (field (name "MP") "WS2812B"))
      (libsource (lib "eagle-import") (part "WS2812B_WS2812B_5050N"))
    )
    (comp (ref "LED36")
      (value "WS2812B_WS2812B_5050N")
      (footprint "eagle-import:WS2812B_WS2812B-NARROW")
      (fields (field (name "MF") "Worldsemi") (field (name "MP") "WS2812B"))
      (libsource (lib "eagle-import") (part "WS2812B_WS2812B_5050N"))
    )
    (comp (ref "LED37")
      (value "WS2812B_WS2812B_5050N")
      (footprint "eagle-import:WS2812B_WS2812B-NARROW")
      (fields (field (name "MF") "Worldsemi") (field (name "MP") "WS2812B"))
      (libsource (lib "eagle-import") (part "WS2812B_WS2812B_5050N"))
    )
    (comp (ref "LED38")
      (value "WS2812B_WS2812B_5050N")
      (footprint "eagle-import:WS2812B_WS2812B-NARROW")
      (fields (field (name "MF") "Worldsemi") (field (name "MP") "WS2812B"))
      (libsource (lib "eagle-import") (part "WS2812B_WS2812B_5050N"))
    )
    (comp (ref "LED39")
      (value "WS2812B_WS2812B_5050N")
      (footprint "eagle-import:WS2812B_WS2812B-NARROW")
      (fields (field (name "MF") "Worldsemi") (field (name "MP") "WS2812B"))
      (libsource (lib "eagle-import") (part "WS2812B_WS2812B_5050N"))
    )
    (comp (ref "LED40")
      (value "WS2812B_WS2812B_5050N")
      (footprint "eagle-import:WS2812B_WS2812B-NARROW")
      (fields (field (name "MF") "Worldsemi") (field (name "MP") "WS2812B"))
      (libsource (lib "eagle-import") (part "WS2812B_WS2812B_5050N"))
    )
    (comp (ref "LED41")
      (value "WS2812B_WS2812B_5050N")
      (footprint "eagle-import:WS2812B_WS2812B-NARROW")
      (fields (field (name "MF") "Worldsemi") (field (name "MP") "WS2812B"))
      (libsource (lib "eagle-import") (part "WS2812B_WS2812B_5050N"))
    )
    (comp (ref "LED42")
      (value "WS2812B_WS2812B_5050N")
      (footprint "eagle-import:WS2812B_WS2812B-NARROW")
      (fields (field (name "MF") "Worldsemi") (field (name "MP") "WS2812B"))
      (libsource (lib "eagle-import") (part "WS2812B_WS2812B_5050N"))
    )
    (comp (ref "LED43")
      (value "WS2812B_WS2812B_5050N")
      (footprint "eagle-import:WS2812B_WS2812B-NARROW")
      (fields (field (name "MF") "Worldsemi") (field (name "MP") "WS2812B"))
      (libsource (lib "eagle-import") (part "WS2812B_WS2812B_5050N"))
    )
    (comp (ref "LED44")
      (value "WS2812B_WS2812B_5050N")
      (footprint "eagle-import:WS2812B_WS2812B-NARROW")
      (fields (field (name "MF") "Worldsemi") (field (name "MP") "WS2812B"))
      (libsource (lib "eagle-import") (part "WS2812B_WS2812B_5050N"))
    )
    (comp (ref "LED45")
      (value "WS2812B_WS2812B_5050N")
      (footprint "eagle-import:WS2812B_WS2812B-NARROW")
      (fields (field (name "MF") "Worldsemi") (field (name "MP") "WS2812B"))
      (libsource (lib "eagle-import") (part "WS2812B_WS2812B_5050N"))
    )
    (comp (ref "LED46")
      (value "WS2812B_WS2812B_5050N")
      (footprint "eagle-import:WS2812B_WS2812B-NARROW")
      (fields (field (name "MF") "Worldsemi") (field (name "MP") "WS2812B"))
      (libsource (lib "eagle-import") (part "WS2812B_WS2812B_5050N"))
    )
    (comp (ref "LED47")
      (value "WS2812B_WS2812B_5050N")
      (footprint "eagle-import:WS2812B_WS2812B-NARROW")
      (fields (field (name "MF") "Worldsemi") (field (name "MP") "WS2812B"))
      (libsource (lib "eagle-import") (part "WS2812B_WS2812B_5050N"))
    )
    (comp (ref "LED48")
      (value "WS2812B_WS2812B_5050N")
      (footprint "eagle-import:WS2812B_WS2812B-NARROW")
      (fields (field (name "MF") "Worldsemi") (field (name "MP") "WS2812B"))
      (libsource (lib "eagle-import") (part "WS2812B_WS2812B_5050N"))
    )
    (comp (ref "LED49")
      (value "WS2812B_WS2812B_5050N")
      (footprint "eagle-import:WS2812B_WS2812B-NARROW")
      (fields (field (name "MF") "Worldsemi") (field (name "MP") "WS2812B"))
      (libsource (lib "eagle-import") (part "WS2812B_WS2812B_5050N"))
    )
    (comp (ref "LED50")
      (value "WS2812B_WS2812B_5050N")
      (footprint "eagle-import:WS2812B_WS2812B-NARROW")
      (fields (field (name "MF") "Worldsemi") (field (name "MP") "WS2812B"))
      (libsource (lib "eagle-import") (part "WS2812B_WS2812B_5050N"))
    )
    (comp (ref "LED51")
      (value "WS2812B_WS2812B_5050N")
      (footprint "eagle-import:WS2812B_WS2812B-NARROW")
      (fields (field (name "MF") "Worldsemi") (field (name "MP") "WS2812B"))
      (libsource (lib "eagle-import") (part "WS2812B_WS2812B_5050N"))
    )
    (comp (ref "LED52")
      (value "WS2812B_WS2812B_5050N")
      (footprint "eagle-import:WS2812B_WS2812B-NARROW")
      (fields (field (name "MF") "Worldsemi") (field (name "MP") "WS2812B"))
      (libsource (lib "eagle-import") (part "WS2812B_WS2812B_5050N"))
    )
    (comp (ref "LED53")
      (value "WS2812B_WS2812B_5050N")
      (footprint "eagle-import:WS2812B_WS2812B-NARROW")
      (fields (field (name "MF") "Worldsemi") (field (name "MP") "WS2812B"))
      (libsource (lib "eagle-import") (part "WS2812B_WS2812B_5050N"))
    )
    (comp (ref "LED54")
      (value "WS2812B_WS2812B_5050N")
      (footprint "eagle-import:WS2812B_WS2812B-NARROW")
      (fields (field (name "MF") "Worldsemi") (field (name "MP") "WS2812B"))
      (libsource (lib "eagle-import") (part "WS2812B_WS2812B_5050N"))
    )
    (comp (ref "LED55")
      (value "WS2812B_WS2812B_5050N")
      (footprint "eagle-import:WS2812B_WS2812B-NARROW")
      (fields (field (name "MF") "Worldsemi") (field (name "MP") "WS2812B"))
      (libsource (lib "eagle-import") (part "WS2812B_WS2812B_5050N"))
    )
    (comp (ref "LED56")
      (value "WS2812B_WS2812B_5050N")
      (footprint "eagle-import:WS2812B_WS2812B-NARROW")
      (fields (field (name "MF") "Worldsemi") (field (name "MP") "WS2812B"))
      (libsource (lib "eagle-import") (part "WS2812B_WS2812B_5050N"))
    )
    (comp (ref "LED57")
      (value "WS2812B_WS2812B_5050N")
      (footprint "eagle-import:WS2812B_WS2812B-NARROW")
      (fields (field (name "MF") "Worldsemi") (field (name "MP") "WS2812B"))
      (libsource (lib "eagle-import") (part "WS2812B_WS2812B_5050N"))
    )
    (comp (ref "LED58")
      (value "WS2812B_WS2812B_5050N")
      (footprint "eagle-import:WS2812B_WS2812B-NARROW")
      (fields (field (name "MF") "Worldsemi") (field (name "MP") "WS2812B"))
      (libsource (lib "eagle-import") (part "WS2812B_WS2812B_5050N"))
    )
    (comp (ref "LED59")
      (value "WS2812B_WS2812B_5050N")
      (footprint "eagle-import:WS2812B_WS2812B-NARROW")
      (fields (field (name "MF") "Worldsemi") (field (name "MP") "WS2812B"))
      (libsource (lib "eagle-import") (part "WS2812B_WS2812B_5050N"))
    )
    (comp (ref "LED60")
      (value "WS2812B_WS2812B_5050N")
      (footprint "eagle-import:WS2812B_WS2812B-NARROW")
      (fields (field (name "MF") "Worldsemi") (field (name "MP") "WS2812B"))
      (libsource (lib "eagle-import") (part "WS2812B_WS2812B_5050N"))
    )
    (comp (ref "LED61")
      (value "WS2812B_WS2812B_5050N")
      (footprint "eagle-import:WS2812B_WS2812B-NARROW")
      (fields (field (name "MF") "Worldsemi") (field (name "MP") "WS2812B"))
      (libsource (lib "eagle-import") (part "WS2812B_WS2812B_5050N"))
    )
    (comp (ref "LED62")
      (value "WS2812B_WS2812B_5050N")
      (footprint "eagle-import:WS2812B_WS2812B-NARROW")
      (fields (field (name "MF") "Worldsemi") (field (name "MP") "WS2812B"))
      (libsource (lib "eagle-import") (part "WS2812B_WS2812B_5050N"))
    )
    (comp (ref "LED63")
      (value "WS2812B_WS2812B_5050N")
      (footprint "eagle-import:WS2812B_WS2812B-NARROW")
      (fields (field (name "MF") "Worldsemi") (field (name "MP") "WS2812B"))
      (libsource (lib "eagle-import") (part "WS2812B_WS2812B_5050N"))
    )
    (comp (ref "LED64")
      (value "WS2812B_WS2812B_5050N")
      (footprint "eagle-import:WS2812B_WS2812B-NARROW")
      (fields (field (name "MF") "Worldsemi") (field (name "MP") "WS2812B"))
      (libsource (lib "eagle-import") (part "WS2812B_WS2812B_5050N"))
    )
    (comp (ref "LED65")
      (value "WS2812B_WS2812B_5050N")
      (footprint "eagle-import:WS2812B_WS2812B-NARROW")
      (fields (field (name "MF") "Worldsemi") (field (name "MP") "WS2812B"))
      (libsource (lib "eagle-import") (part "WS2812B_WS2812B_5050N"))
    )
    (comp (ref "LED66")
      (value "WS2812B_WS2812B_5050N")
      (footprint "eagle-import:WS2812B_WS2812B-NARROW")
      (fields (field (name "MF") "Worldsemi") (field (name "MP") "WS2812B"))
      (libsource (lib "eagle-import") (part "WS2812B_WS2812B_5050N"))
    )
    (comp (ref "LED67")
      (value "WS2812B_WS2812B_5050N")
      (footprint "eagle-import:WS2812B_WS2812B-NARROW")
      (fields (field (name "MF") "Worldsemi") (field (name "MP") "WS2812B"))
      (libsource (lib "eagle-import") (part "WS2812B_WS2812B_5050N"))
    )
    (comp (ref "LED68")
      (value "WS2812B_WS2812B_5050N")
      (footprint "eagle-import:WS2812B_WS2812B-NARROW")
      (fields (field (name "MF") "Worldsemi") (field (name "MP") "WS2812B"))
      (libsource (lib "eagle-import") (part "WS2812B_WS2812B_5050N"))
    )
    (comp (ref "LED69")
      (value "WS2812B_WS2812B_5050N")
      (footprint "eagle-import:WS2812B_WS2812B-NARROW")
      (fields (field (name "MF") "Worldsemi") (field (name "MP") "WS2812B"))
      (libsource (lib "eagle-import") (part "WS2812B_WS2812B_5050N"))
    )
    (comp (ref "LED70")
      (value "WS2812B_WS2812B_5050N")
      (footprint "eagle-import:WS2812B_WS2812B-NARROW")
      (fields (field (name "MF") "Worldsemi") (field (name "MP") "WS2812B"))
      (libsource (lib "eagle-import") (part "WS2812B_WS2812B_5050N"))
    )
    (comp (ref "LED71")
      (value "WS2812B_WS2812B_5050N")
      (footprint "eagle-import:WS2812B_WS2812B-NARROW")
      (fields (field (name "MF") "Worldsemi") (field (name "MP") "WS2812B"))
      (libsource (lib "eagle-import") (part "WS2812B_WS2812B_5050N"))
    )
    (comp (ref "LED72")
      (value "WS2812B_WS2812B_5050N")
      (footprint "eagle-import:WS2812B_WS2812B-NARROW")
      (fields (field (name "MF") "Worldsemi") (field (name "MP") "WS2812B"))
      (libsource (lib "eagle-import") (part "WS2812B_WS2812B_5050N"))
    )
    (comp (ref "LED73")
      (value "WS2812B_WS2812B_5050N")
      (footprint "eagle-import:WS2812B_WS2812B-NARROW")
      (fields (field (name "MF") "Worldsemi") (field (name "MP") "WS2812B"))
      (libsource (lib "eagle-import") (part "WS2812B_WS2812B_5050N"))
    )
    (comp (ref "LED74")
      (value "WS2812B_WS2812B_5050N")
      (footprint "eagle-import:WS2812B_WS2812B-NARROW")
      (fields (field (name "MF") "Worldsemi") (field (name "MP") "WS2812B"))
      (libsource (lib "eagle-import") (part "WS2812B_WS2812B_5050N"))
    )
    (comp (ref "LED75")
      (value "WS2812B_WS2812B_5050N")
      (footprint "eagle-import:WS2812B_WS2812B-NARROW")
      (fields (field (name "MF") "Worldsemi") (field (name "MP") "WS2812B"))
      (libsource (lib "eagle-import") (part "WS2812B_WS2812B_5050N"))
    )
    (comp (ref "LED76")
      (value "WS2812B_WS2812B_5050N")
      (footprint "eagle-import:WS2812B_WS2812B-NARROW")
      (fields (field (name "MF") "Worldsemi") (field (name "MP") "WS2812B"))
      (libsource (lib "eagle-import") (part "WS2812B_WS2812B_5050N"))
    )
    (comp (ref "LED77")
      (value "WS2812B_WS2812B_5050N")
      (footprint "eagle-import:WS2812B_WS2812B-NARROW")
      (fields (field (name "MF") "Worldsemi") (field (name "MP") "WS2812B"))
      (libsource (lib "eagle-import") (part "WS2812B_WS2812B_5050N"))
    )
    (comp (ref "LED78")
      (value "WS2812B_WS2812B_5050N")
      (footprint "eagle-import:WS2812B_WS2812B-NARROW")
      (fields (field (name "MF") "Worldsemi") (field (name "MP") "WS2812B"))
      (libsource (lib "eagle-import") (part "WS2812B_WS2812B_5050N"))
    )
    (comp (ref "LED79")
      (value "WS2812B_WS2812B_5050N")
      (footprint "eagle-import:WS2812B_WS2812B-NARROW")
      (fields (field (name "MF") "Worldsemi") (field (name "MP") "WS2812B"))
      (libsource (lib "eagle-import") (part "WS2812B_WS2812B_5050N"))
    )
    (comp (ref "LED80")
      (value "WS2812B_WS2812B_5050N")
      (footprint "eagle-import:WS2812B_WS2812B-NARROW")
      (fields (field (name "MF") "Worldsemi") (field (name "MP") "WS2812B"))
      (libsource (lib "eagle-import") (part "WS2812B_WS2812B_5050N"))
    )
    (comp (ref "LED81")
      (value "WS2812B_WS2812B_5050N")
      (footprint "eagle-import:WS2812B_WS2812B-NARROW")
      (fields (field (name "MF") "Worldsemi") (field (name "MP") "WS2812B"))
      (libsource (lib "eagle-import") (part "WS2812B_WS2812B_5050N"))
    )
    (comp (ref "LED82")
      (value "WS2812B_WS2812B_5050N")
      (footprint "eagle-import:WS2812B_WS2812B-NARROW")
      (fields (field (name "MF") "Worldsemi") (field (name "MP") "WS2812B"))
      (libsource (lib "eagle-import") (part "WS2812B_WS2812B_5050N"))
    )
    (comp (ref "LED83")
      (value "WS2812B_WS2812B_5050N")
      (footprint "eagle-import:WS2812B_WS2812B-NARROW")
      (fields (field (name "MF") "Worldsemi") (field (name "MP") "WS2812B"))
      (libsource (lib "eagle-import") (part "WS2812B_WS2812B_5050N"))
    )
    (comp (ref "LED84")
      (value "WS2812B_WS2812B_5050N")
      (footprint "eagle-import:WS2812B_WS2812B-NARROW")
      (fields (field (name "MF") "Worldsemi") (field (name "MP") "WS2812B"))
      (libsource (lib "eagle-import") (part "WS2812B_WS2812B_5050N"))
    )
    (comp (ref "LED85")
      (value "WS2812B_WS2812B_5050N")
      (footprint "eagle-import:WS2812B_WS2812B-NARROW")
      (fields (field (name "MF") "Worldsemi") (field (name "MP") "WS2812B"))
      (libsource (lib "eagle-import") (part "WS2812B_WS2812B_5050N"))
    )
    (comp (ref "LED86")
      (value "WS2812B_WS2812B_5050N")
      (footprint "eagle-import:WS2812B_WS2812B-NARROW")
      (fields (field (name "MF") "Worldsemi") (field (name "MP") "WS2812B"))
      (libsource (lib "eagle-import") (part "WS2812B_WS2812B_5050N"))
    )
    (comp (ref "LED87")
      (value "WS2812B_WS2812B_5050N")
      (footprint "eagle-import:WS2812B_WS2812B-NARROW")
      (fields (field (name "MF") "Worldsemi") (field (name "MP") "WS2812B"))
      (libsource (lib "eagle-import") (part "WS2812B_WS2812B_5050N"))
    )
    (comp (ref "LED88")
      (value "WS2812B_WS2812B_5050N")
      (footprint "eagle-import:WS2812B_WS2812B-NARROW")
      (fields (field (name "MF") "Worldsemi") (field (name "MP") "WS2812B"))
      (libsource (lib "eagle-import") (part "WS2812B_WS2812B_5050N"))
    )
    (comp (ref "LED89")
      (value "WS2812B_WS2812B_5050N")
      (footprint "eagle-import:WS2812B_WS2812B-NARROW")
      (fields (field (name "MF") "Worldsemi") (field (name "MP") "WS2812B"))
      (libsource (lib "eagle-import") (part "WS2812B_WS2812B_5050N"))
    )
    (comp (ref "LED90")
      (value "WS2812B_WS2812B_5050N")
      (footprint "eagle-import:WS2812B_WS2812B-NARROW")
      (fields (field (name "MF") "Worldsemi") (field (name "MP") "WS2812B"))
      (libsource (lib "eagle-import") (part "WS2812B_WS2812B_5050N"))
    )
    (comp (ref "LED91")
      (value "WS2812B_WS2812B_5050N")
      (footprint "eagle-import:WS2812B_WS2812B-NARROW")
      (fields (field (name "MF") "Worldsemi") (field (name "MP") "WS2812B"))
      (libsource (lib "eagle-import") (part "WS2812B_WS2812B_5050N"))
    )
    (comp (ref "LED92")
      (value "WS2812B_WS2812B_5050N")
      (footprint "eagle-import:WS2812B_WS2812B-NARROW")
      (fields (field (name "MF") "Worldsemi") (field (name "MP") "WS2812B"))
      (libsource (lib "eagle-import") (part "WS2812B_WS2812B_5050N"))
    )
    (comp (ref "LED93")
      (value "WS2812B_WS2812B_5050N")
      (footprint "eagle-import:WS2812B_WS2812B-NARROW")
      (fields (field (name "MF") "Worldsemi") (field (name "MP") "WS2812B"))
      (libsource (lib "eagle-import") (part "WS2812B_WS2812B_5050N"))
    )
    (comp (ref "LED94")
      (value "WS2812B_WS2812B_5050N")
      (footprint "eagle-import:WS2812B_WS2812B-NARROW")
      (fields (field (name "MF") "Worldsemi") (field (name "MP") "WS2812B"))
      (libsource (lib "eagle-import") (part "WS2812B_WS2812B_5050N"))
    )
    (comp (ref "LED95")
      (value "WS2812B_WS2812B_5050N")
      (footprint "eagle-import:WS2812B_WS2812B-NARROW")
      (fields (field (name "MF") "Worldsemi") (field (name "MP") "WS2812B"))
      (libsource (lib "eagle-import") (part "WS2812B_WS2812B_5050N"))
    )
    (comp (ref "LED96")
      (value "WS2812B_WS2812B_5050N")
      (footprint "eagle-import:WS2812B_WS2812B-NARROW")
      (fields (field (name "MF") "Worldsemi") (field (name "MP") "WS2812B"))
      (libsource (lib "eagle-import") (part "WS2812B_WS2812B_5050N"))
    )
    (comp (ref "LED97")
      (value "WS2812B_WS2812B_5050N")
      (footprint "eagle-import:WS2812B_WS2812B-NARROW")
      (fields (field (name "MF") "Worldsemi") (field (name "MP") "WS2812B"))
      (libsource (lib "eagle-import") (part "WS2812B_WS2812B_5050N"))
    )
    (comp (ref "LED98")
      (value "WS2812B_WS2812B_5050N")
      (footprint "eagle-import:WS2812B_WS2812B-NARROW")
      (fields (field (name "MF") "Worldsemi") (field (name "MP") "WS2812B"))
      (libsource (lib "eagle-import") (part "WS2812B_WS2812B_5050N"))
    )
    (comp (ref "LED99")
      (value "WS2812B_WS2812B_5050N")
      (footprint "eagle-import:WS2812B_WS2812B-NARROW")
      (fields (field (name "MF") "Worldsemi") (field (name "MP") "WS2812B"))
      (libsource (lib "eagle-import") (part "WS2812B_WS2812B_5050N"))
    )
    (comp (ref "R1")
      (value "10K")
      (footprint "eagle-import:Y-RES_RESC2012X65")
      (libsource (lib "eagle-import") (part "Y-RES_RCHIP-0805(2012-METRIC)_"))
    )
    (comp (ref "R2")
      (value "10K")
      (footprint "eagle-import:Y-RES_RESC2012X65")
      (libsource (lib "eagle-import") (part "Y-RES_RCHIP-0805(2012-METRIC)_"))
    )
    (comp (ref "R3")
      (value "22R")
      (footprint "eagle-import:Y-RES_RESC2012X65")
      (libsource (lib "eagle-import") (part "Y-RES_RCHIP-0805(2012-METRIC)_"))
    )
    (comp (ref "R4")
      (value "22R")
      (footprint "eagle-import:Y-RES_RESC2012X65")
      (libsource (lib "eagle-import") (part "Y-RES_RCHIP-0805(2012-METRIC)_"))
    )
    (comp (ref "R5")
      (value "10K")
      (footprint "eagle-import:Y-RES_RESC2012X65")
      (libsource (lib "eagle-import") (part "Y-RES_RCHIP-0805(2012-METRIC)_"))
    )
    (comp (ref "R6")
      (value "10K")
      (footprint "eagle-import:Y-RES_RESC2012X65")
      (libsource (lib "eagle-import") (part "Y-RES_RCHIP-0805(2012-METRIC)_"))
    )
    (comp (ref "R7")
      (value "330R")
      (footprint "eagle-import:Y-RES_RESC2012X65")
      (libsource (lib "eagle-import") (part "Y-RES_RCHIP-0805(2012-METRIC)_"))
    )
    (comp (ref "R8")
      (value "10K")
      (footprint "eagle-import:Y-RES_RESC2012X65")
      (libsource (lib "eagle-import") (part "Y-RES_RCHIP-0805(2012-METRIC)_"))
    )
    (comp (ref "R9")
      (value "10K")
      (footprint "eagle-import:Y-RES_RESC2012X65")
      (libsource (lib "eagle-import") (part "Y-RES_RCHIP-0805(2012-METRIC)_"))
    )
    (comp (ref "R10")
      (value "10K")
      (footprint "eagle-import:Y-RES_RESC2012X65")
      (libsource (lib "eagle-import") (part "Y-RES_RCHIP-0805(2012-METRIC)_"))
    )
    (comp (ref "R11")
      (value "10K")
      (footprint "eagle-import:Y-RES_RESC2012X65")
      (libsource (lib "eagle-import") (part "Y-RES_RCHIP-0805(2012-METRIC)_"))
    )
    (comp (ref "R12")
      (value "10K")
      (footprint "eagle-import:Y-RES_RESC2012X65")
      (libsource (lib "eagle-import") (part "Y-RES_RCHIP-0805(2012-METRIC)_"))
    )
    (comp (ref "R13")
      (value "10K")
      (footprint "eagle-import:Y-RES_RESC2012X65")
      (libsource (lib "eagle-import") (part "Y-RES_RCHIP-0805(2012-METRIC)_"))
    )
    (comp (ref "R14")
      (value "10K")
      (footprint "eagle-import:Y-RES_RESC2012X65")
      (libsource (lib "eagle-import") (part "Y-RES_RCHIP-0805(2012-METRIC)_"))
    )
    (comp (ref "R15")
      (value "10K")
      (footprint "eagle-import:Y-RES_RESC2012X65")
      (libsource (lib "eagle-import") (part "Y-RES_RCHIP-0805(2012-METRIC)_"))
    )
    (comp (ref "R16")
      (value "2k2")
      (footprint "eagle-import:Y-RES_RESC2012X65")
      (libsource (lib "eagle-import") (part "Y-RES_RCHIP-0805(2012-METRIC)_"))
    )
    (comp (ref "R17")
      (value "2k2")
      (footprint "eagle-import:Y-RES_RESC2012X65")
      (libsource (lib "eagle-import") (part "Y-RES_RCHIP-0805(2012-METRIC)_"))
    )
    (comp (ref "R18")
      (value "3K3")
      (footprint "eagle-import:Y-RES_RESC2012X65")
      (libsource (lib "eagle-import") (part "Y-RES_RCHIP-0805(2012-METRIC)_"))
    )
    (comp (ref "R19")
      (value "3K3")
      (footprint "eagle-import:Y-RES_RESC2012X65")
      (libsource (lib "eagle-import") (part "Y-RES_RCHIP-0805(2012-METRIC)_"))
    )
    (comp (ref "R20")
      (value "3K3")
      (footprint "eagle-import:Y-RES_RESC2012X65")
      (libsource (lib "eagle-import") (part "Y-RES_RCHIP-0805(2012-METRIC)_"))
    )
    (comp (ref "R21")
      (value "2k2")
      (footprint "eagle-import:Y-RES_RESC2012X65")
      (libsource (lib "eagle-import") (part "Y-RES_RCHIP-0805(2012-METRIC)_"))
    )
    (comp (ref "S0")
      (value "1-LAYER_SWITCH_PCB_B3F-10-XX0.5")
      (footprint "eagle-import:1-LAYER_B3F-10XXROC")
      (fields (field (name "MPN") "B3F-1000"))
      (libsource (lib "eagle-import") (part "1-LAYER_SWITCH_PCB_B3F-10-XX0.5"))
    )
    (comp (ref "S1")
      (value "1-LAYER_SWITCH_PCB_B3F-10-XX0.5")
      (footprint "eagle-import:1-LAYER_B3F-10XXROC")
      (fields (field (name "MPN") "B3F-1000"))
      (libsource (lib "eagle-import") (part "1-LAYER_SWITCH_PCB_B3F-10-XX0.5"))
    )
    (comp (ref "S2")
      (value "1-LAYER_SWITCH_PCB_B3F-10-XX0.5")
      (footprint "eagle-import:1-LAYER_B3F-10XXROC")
      (fields (field (name "MPN") "B3F-1000"))
      (libsource (lib "eagle-import") (part "1-LAYER_SWITCH_PCB_B3F-10-XX0.5"))
    )
    (comp (ref "S3")
      (value "1-LAYER_SWITCH_PCB_B3F-10-XX0.5")
      (footprint "eagle-import:1-LAYER_B3F-10XXROC")
      (fields (field (name "MPN") "B3F-1000"))
      (libsource (lib "eagle-import") (part "1-LAYER_SWITCH_PCB_B3F-10-XX0.5"))
    )
    (comp (ref "S4")
      (value "1-LAYER_SWITCH_PCB_B3F-10-XX0.5")
      (footprint "eagle-import:1-LAYER_B3F-10XXROC")
      (fields (field (name "MPN") "B3F-1000"))
      (libsource (lib "eagle-import") (part "1-LAYER_SWITCH_PCB_B3F-10-XX0.5"))
    )
    (comp (ref "S5")
      (value "1-LAYER_SWITCH_PCB_B3F-10-XX0.5")
      (footprint "eagle-import:1-LAYER_B3F-10XXROC")
      (fields (field (name "MPN") "B3F-1000"))
      (libsource (lib "eagle-import") (part "1-LAYER_SWITCH_PCB_B3F-10-XX0.5"))
    )
    (comp (ref "S6")
      (value "1-LAYER_SWITCH_PCB_B3F-10-XX0.5")
      (footprint "eagle-import:1-LAYER_B3F-10XXROC")
      (fields (field (name "MPN") "B3F-1000"))
      (libsource (lib "eagle-import") (part "1-LAYER_SWITCH_PCB_B3F-10-XX0.5"))
    )
    (comp (ref "S7")
      (value "1-LAYER_SWITCH_PCB_B3F-10-XX0.5")
      (footprint "eagle-import:1-LAYER_B3F-10XXROC")
      (fields (field (name "MPN") "B3F-1000"))
      (libsource (lib "eagle-import") (part "1-LAYER_SWITCH_PCB_B3F-10-XX0.5"))
    )
    (comp (ref "S8")
      (value "1-LAYER_SWITCH_PCB_B3F-10-XX0.5")
      (footprint "eagle-import:1-LAYER_B3F-10XXROC")
      (fields (field (name "MPN") "B3F-1000"))
      (libsource (lib "eagle-import") (part "1-LAYER_SWITCH_PCB_B3F-10-XX0.5"))
    )
    (comp (ref "S9")
      (value "1-LAYER_SWITCH_PCB_B3F-10-XX0.5")
      (footprint "eagle-import:1-LAYER_B3F-10XXROC")
      (fields (field (name "MPN") "B3F-1000"))
      (libsource (lib "eagle-import") (part "1-LAYER_SWITCH_PCB_B3F-10-XX0.5"))
    )
    (comp (ref "SR")
      (value "1-LAYER_SWITCH_PCB_B3F-10-XX0.5")
      (footprint "eagle-import:1-LAYER_B3F-10XXROC")
      (fields (field (name "MPN") "B3F-1000"))
      (libsource (lib "eagle-import") (part "1-LAYER_SWITCH_PCB_B3F-10-XX0.5"))
    )
    (comp (ref "U$1")
      (value "Y_CONECTOR_POGOPAD2")
      (footprint "eagle-import:Y_CONECTOR_POGOPAD_50")
      (libsource (lib "eagle-import") (part "Y_CONECTOR_POGOPAD2"))
    )
    (comp (ref "U$2")
      (value "Y_CONECTOR_POGOPAD2")
      (footprint "eagle-import:Y_CONECTOR_POGOPAD_50")
      (libsource (lib "eagle-import") (part "Y_CONECTOR_POGOPAD2"))
    )
    (comp (ref "U$3")
      (value "Y_CONECTOR_POGOPAD2")
      (footprint "eagle-import:Y_CONECTOR_POGOPAD_50")
      (libsource (lib "eagle-import") (part "Y_CONECTOR_POGOPAD2"))
    )
    (comp (ref "U1")
      (value "DS1302ZN_T_R_DS1302ZN+T&R")
      (footprint "eagle-import:DS1302ZN_T_R_SOIC127P600X175-8N")
      (fields (field (name "MF") "Analog Devices") (field (name "MP") "DS1302ZN+T&amp;R"))
      (libsource (lib "eagle-import") (part "DS1302ZN_T_R_DS1302ZN+T&R"))
    )
    (comp (ref "U2")
      (value "Y_COMP-SET_ESP32-S3-WROOM-1-N16R2")
      (footprint "eagle-import:Y_COMP-SET_XCVR_ESP32-S3-WROOM-1-N16R2")
      (fields (field (name "MF") "Espressif Systems") (field (name "MP") "ESP32-S3-WROOM-1-N16R2"))
      (libsource (lib "eagle-import") (part "Y_COMP-SET_ESP32-S3-WROOM-1-N16R2"))
    )
    (comp (ref "VR1")
      (value "UA78M33CDCYG3_UA78M33CDCYG3")
      (footprint "eagle-import:UA78M33CDCYG3_VREG_UA78M33CDCYG3")
      (fields (field (name "MF") "Texas Instruments") (field (name "MP") "UA78M33CDCYG3"))
      (libsource (lib "eagle-import") (part "UA78M33CDCYG3_UA78M33CDCYG3"))
    )
    (comp (ref "Y1")
      (value "WE-XTAL_WATCH_WE-XTAL_WATCH_2X6")
      (footprint "eagle-import:WE-XTAL_WATCH_WE-XTAL_WATCH-2X6")
      (fields (field (name "MF") "Würth Elektronik") (field (name "MP") "830014219B"))
      (libsource (lib "eagle-import") (part "WE-XTAL_WATCH_WE-XTAL_WATCH_2X6"))
    )
  )
  (nets
    (net (code "1") (name "/CLOK") (class "Default")
      (node (ref "U1") (pin "7") (pinfunction "SCLK_7") (pintype "input"))
      (node (ref "U2") (pin "20") (pinfunction "IO12_20") (pintype "bidirectional"))
    )
    (net (code "2") (name "/CS") (class "Default")
      (node (ref "R16") (pin "2") (pinfunction "2_2") (pintype "passive"))
      (node (ref "U2") (pin "17") (pinfunction "IO9_17") (pintype "bidirectional"))
    )
    (net (code "3") (name "/DATA") (class "Default")
      (node (ref "U1") (pin "6") (pinfunction "I/O_6") (pintype "bidirectional"))
      (node (ref "U2") (pin "19") (pinfunction "IO11_19") (pintype "bidirectional"))
    )
    (net (code "4") (name "/IO0") (class "Default")
      (node (ref "R5") (pin "1") (pinfunction "1_1") (pintype "passive"))
      (node (ref "S0") (pin "1") (pinfunction "S_1") (pintype "passive"))
      (node (ref "S0") (pin "2") (pinfunction "S1_2") (pintype "passive"))
      (node (ref "U2") (pin "27") (pinfunction "IO0_27") (pintype "bidirectional"))
    )
    (net (code "5") (name "/J-P1") (class "Default")
      (node (ref "JP1") (pin "1") (pinfunction "1_1") (pintype "passive"))
      (node (ref "U2") (pin "4") (pinfunction "IO4_4") (pintype "bidirectional"))
    )
    (net (code "6") (name "/J-P2") (class "Default")
      (node (ref "JP1") (pin "2") (pinfunction "2_2") (pintype "passive"))
      (node (ref "U2") (pin "5") (pinfunction "IO5_5") (pintype "bidirectional"))
    )
    (net (code "7") (name "/J-P3") (class "Default")
      (node (ref "JP1") (pin "3") (pinfunction "3_3") (pintype "passive"))
      (node (ref "U2") (pin "6") (pinfunction "IO6_6") (pintype "bidirectional"))
    )
    (net (code "8") (name "/J-P4") (class "Default")
      (node (ref "JP1") (pin "4") (pinfunction "4_4") (pintype "passive"))
      (node (ref "U2") (pin "7") (pinfunction "IO7_7") (pintype "bidirectional"))
    )
    (net (code "9") (name "/J-P5") (class "Default")
      (node (ref "JP1") (pin "5") (pinfunction "5_5") (pintype "passive"))
      (node (ref "U2") (pin "8") (pinfunction "IO15_8") (pintype "bidirectional"))
    )
    (net (code "10") (name "/J-P6") (class "Default")
      (node (ref "JP1") (pin "6") (pinfunction "6_6") (pintype "passive"))
      (node (ref "U2") (pin "9") (pinfunction "IO16_9") (pintype "bidirectional"))
    )
    (net (code "11") (name "/J-P7") (class "Default")
      (node (ref "JP1") (pin "7") (pinfunction "7_7") (pintype "passive"))
      (node (ref "U2") (pin "10") (pinfunction "IO17_10") (pintype "bidirectional"))
    )
    (net (code "12") (name "/J-P8") (class "Default")
      (node (ref "JP1") (pin "8") (pinfunction "8_8") (pintype "passive"))
      (node (ref "U2") (pin "11") (pinfunction "IO18_11") (pintype "bidirectional"))
    )
    (net (code "13") (name "/J-P9") (class "Default")
      (node (ref "JP1") (pin "9") (pinfunction "9_9") (pintype "passive"))
      (node (ref "U2") (pin "12") (pinfunction "IO8_12") (pintype "bidirectional"))
    )
    (net (code "14") (name "/LED_DATA") (class "Default")
      (node (ref "LED1") (pin "4-DIN") (pinfunction "DI_4-DIN") (pintype "input"))
      (node (ref "U2") (pin "39") (pinfunction "IO1_39") (pintype "bidirectional"))
    )
    (net (code "15") (name "/MISO") (class "Default")
      (node (ref "J1") (pin "7") (pinfunction "DAT0_7") (pintype "bidirectional"))
      (node (ref "R15") (pin "2") (pinfunction "2_2") (pintype "passive"))
      (node (ref "U2") (pin "22") (pinfunction "IO14_22") (pintype "bidirectional"))
    )
    (net (code "16") (name "/MOSI") (class "Default")
      (node (ref "R17") (pin "2") (pinfunction "2_2") (pintype "passive"))
      (node (ref "U2") (pin "21") (pinfunction "IO13_21") (pintype "bidirectional"))
    )
    (net (code "17") (name "/RESET_C") (class "Default")
      (node (ref "U1") (pin "5") (pinfunction "CE_5") (pintype "input"))
      (node (ref "U2") (pin "18") (pinfunction "IO10_18") (pintype "bidirectional"))
    )
    (net (code "18") (name "/S1") (class "Default")
      (node (ref "C113") (pin "2") (pinfunction "2_2") (pintype "passive"))
      (node (ref "R12") (pin "1") (pinfunction "1_1") (pintype "passive"))
      (node (ref "S1") (pin "1") (pinfunction "S_1") (pintype "passive"))
      (node (ref "S1") (pin "2") (pinfunction "S1_2") (pintype "passive"))
      (node (ref "U2") (pin "34") (pinfunction "IO41_34") (pintype "bidirectional"))
    )
    (net (code "19") (name "/S2") (class "Default")
      (node (ref "C18") (pin "2") (pinfunction "2_2") (pintype "passive"))
      (node (ref "R9") (pin "1") (pinfunction "1_1") (pintype "passive"))
      (node (ref "S2") (pin "1") (pinfunction "S_1") (pintype "passive"))
      (node (ref "S2") (pin "2") (pinfunction "S1_2") (pintype "passive"))
      (node (ref "U2") (pin "35") (pinfunction "IO42_35") (pintype "bidirectional"))
    )
    (net (code "20") (name "/S3") (class "Default")
      (node (ref "C110") (pin "2") (pinfunction "2_2") (pintype "passive"))
      (node (ref "R10") (pin "1") (pinfunction "1_1") (pintype "passive"))
      (node (ref "S3") (pin "1") (pinfunction "S_1") (pintype "passive"))
      (node (ref "S3") (pin "2") (pinfunction "S1_2") (pintype "passive"))
      (node (ref "U2") (pin "38") (pinfunction "IO2_38") (pintype "bidirectional"))
    )
    (net (code "21") (name "/S4") (class "Default")
      (node (ref "C114") (pin "2") (pinfunction "2_2") (pintype "passive"))
      (node (ref "R13") (pin "1") (pinfunction "1_1") (pintype "passive"))
      (node (ref "S4") (pin "1") (pinfunction "S_1") (pintype "passive"))
      (node (ref "S4") (pin "2") (pinfunction "S1_2") (pintype "passive"))
      (node (ref "U2") (pin "31") (pinfunction "IO38_31") (pintype "bidirectional"))
    )
    (net (code "22") (name "/S5") (class "Default")
      (node (ref "C14") (pin "2") (pinfunction "2_2") (pintype "passive"))
      (node (ref "R1") (pin "1") (pinfunction "1_1") (pintype "passive"))
      (node (ref "S5") (pin "1") (pinfunction "S_1") (pintype "passive"))
      (node (ref "S5") (pin "2") (pinfunction "S1_2") (pintype "passive"))
      (node (ref "U2") (pin "32") (pinfunction "IO39_32") (pintype "bidirectional"))
    )
    (net (code "23") (name "/S6") (class "Default")
      (node (ref "C17") (pin "2") (pinfunction "2_2") (pintype "passive"))
      (node (ref "R2") (pin "1") (pinfunction "1_1") (pintype "passive"))
      (node (ref "S6") (pin "1") (pinfunction "S_1") (pintype "passive"))
      (node (ref "S6") (pin "2") (pinfunction "S1_2") (pintype "passive"))
      (node (ref "U2") (pin "33") (pinfunction "IO40_33") (pintype "bidirectional"))
    )
    (net (code "24") (name "/S7") (class "Default")
      (node (ref "C115") (pin "2") (pinfunction "2_2") (pintype "passive"))
      (node (ref "R14") (pin "1") (pinfunction "1_1") (pintype "passive"))
      (node (ref "S7") (pin "1") (pinfunction "S_1") (pintype "passive"))
      (node (ref "S7") (pin "2") (pinfunction "S1_2") (pintype "passive"))
      (node (ref "U2") (pin "28") (pinfunction "IO35_28") (pintype "bidirectional"))
    )
    (net (code "25") (name "/S8") (class "Default")
      (node (ref "C111") (pin "2") (pinfunction "2_2") (pintype "passive"))
      (node (ref "R8") (pin "1") (pinfunction "1_1") (pintype "passive"))
      (node (ref "S8") (pin "1") (pinfunction "S_1") (pintype "passive"))
      (node (ref "S8") (pin "2") (pinfunction "S1_2") (pintype "passive"))
      (node (ref "U2") (pin "29") (pinfunction "IO36_29") (pintype "bidirectional"))
    )
    (net (code "26") (name "/S9") (class "Default")
      (node (ref "C112") (pin "2") (pinfunction "2_2") (pintype "passive"))
      (node (ref "R11") (pin "1") (pinfunction "1_1") (pintype "passive"))
      (node (ref "S9") (pin "1") (pinfunction "S_1") (pintype "passive"))
      (node (ref "S9") (pin "2") (pinfunction "S1_2") (pintype "passive"))
      (node (ref "U2") (pin "30") (pinfunction "IO37_30") (pintype "bidirectional"))
    )
    (net (code "27") (name "/SCLK") (class "Default")
      (node (ref "R21") (pin "2") (pinfunction "2_2") (pintype "passive"))
      (node (ref "U2") (pin "23") (pinfunction "IO21_23") (pintype "bidirectional"))
    )
    (net (code "28") (name "/USB_N") (class "Default")
      (node (ref "J2") (pin "A7") (pinfunction "DN1_A7") (pintype "passive"))
      (node (ref "J2") (pin "B7") (pinfunction "DN2_B7") (pintype "passive"))
      (node (ref "R3") (pin "2") (pinfunction "2_2") (pintype "passive"))
    )
    (net (code "29") (name "/USB_P") (class "Default")
      (node (ref "J2") (pin "A6") (pinfunction "DP1_A6") (pintype "passive"))
      (node (ref "J2") (pin "B6") (pinfunction "DP2_B6") (pintype "passive"))
      (node (ref "R4") (pin "2") (pinfunction "2_2") (pintype "passive"))
    )
    (net (code "30") (name "Net-(D226-A)") (class "Default")
      (node (ref "D226") (pin "1") (pinfunction "A_1") (pintype "passive"))
      (node (ref "R7") (pin "2") (pinfunction "2_2") (pintype "passive"))
    )
    (net (code "31") (name "Net-(J1-CLK)") (class "Default")
      (node (ref "J1") (pin "5") (pinfunction "CLK_5") (pintype "bidirectional"))
      (node (ref "R18") (pin "1") (pinfunction "1_1") (pintype "passive"))
      (node (ref "R21") (pin "1") (pinfunction "1_1") (pintype "passive"))
    )
    (net (code "32") (name "Net-(J1-CMD)") (class "Default")
      (node (ref "J1") (pin "2") (pinfunction "CMD_2") (pintype "bidirectional"))
      (node (ref "R17") (pin "1") (pinfunction "1_1") (pintype "passive"))
      (node (ref "R19") (pin "1") (pinfunction "1_1") (pintype "passive"))
    )
    (net (code "33") (name "Net-(J1-DAT3{slash}CD)") (class "Default")
      (node (ref "J1") (pin "1") (pinfunction "DAT3/CD_1") (pintype "bidirectional"))
      (node (ref "R16") (pin "1") (pinfunction "1_1") (pintype "passive"))
      (node (ref "R20") (pin "1") (pinfunction "1_1") (pintype "passive"))
    )
    (net (code "34") (name "Net-(LED1-DO)") (class "Default")
      (node (ref "LED1") (pin "2-DOUT") (pinfunction "DO_2-DOUT") (pintype "output"))
      (node (ref "LED2") (pin "4-DIN") (pinfunction "DI_4-DIN") (pintype "input"))
    )
    (net (code "35") (name "Net-(LED2-DO)") (class "Default")
      (node (ref "LED2") (pin "2-DOUT") (pinfunction "DO_2-DOUT") (pintype "output"))
      (node (ref "LED3") (pin "4-DIN") (pinfunction "DI_4-DIN") (pintype "input"))
    )
    (net (code "36") (name "Net-(LED3-DO)") (class "Default")
      (node (ref "LED3") (pin "2-DOUT") (pinfunction "DO_2-DOUT") (pintype "output"))
      (node (ref "LED4") (pin "4-DIN") (pinfunction "DI_4-DIN") (pintype "input"))
    )
    (net (code "37") (name "Net-(LED4-DO)") (class "Default")
      (node (ref "LED4") (pin "2-DOUT") (pinfunction "DO_2-DOUT") (pintype "output"))
      (node (ref "LED5") (pin "4-DIN") (pinfunction "DI_4-DIN") (pintype "input"))
    )
    (net (code "38") (name "Net-(LED6-DI)") (class "Default")
      (node (ref "LED6") (pin "4-DIN") (pinfunction "DI_4-DIN") (pintype "input"))
      (node (ref "LED7") (pin "2-DOUT") (pinfunction "DO_2-DOUT") (pintype "output"))
    )
    (net (code "39") (name "Net-(LED7-DI)") (class "Default")
      (node (ref "LED7") (pin "4-DIN") (pinfunction "DI_4-DIN") (pintype "input"))
      (node (ref "LED8") (pin "2-DOUT") (pinfunction "DO_2-DOUT") (pintype "output"))
    )
    (net (code "40") (name "Net-(LED8-DI)") (class "Default")
      (node (ref "LED8") (pin "4-DIN") (pinfunction "DI_4-DIN") (pintype "input"))
      (node (ref "LED9") (pin "2-DOUT") (pinfunction "DO_2-DOUT") (pintype "output"))
    )
    (net (code "41") (name "Net-(LED10-DI)") (class "Default")
      (node (ref "LED10") (pin "4-DIN") (pinfunction "DI_4-DIN") (pintype "input"))
      (node (ref "LED11") (pin "2-DOUT") (pinfunction "DO_2-DOUT") (pintype "output"))
    )
    (net (code "42") (name "Net-(LED10-DO)") (class "Default")
      (node (ref "LED10") (pin "2-DOUT") (pinfunction "DO_2-DOUT") (pintype "output"))
      (node (ref "LED9") (pin "4-DIN") (pinfunction "DI_4-DIN") (pintype "input"))
    )
    (net (code "43") (name "Net-(LED11-DI)") (class "Default")
      (node (ref "LED11") (pin "4-DIN") (pinfunction "DI_4-DIN") (pintype "input"))
      (node (ref "LED12") (pin "2-DOUT") (pinfunction "DO_2-DOUT") (pintype "output"))
    )
    (net (code "44") (name "Net-(LED12-DI)") (class "Default")
      (node (ref "LED12") (pin "4-DIN") (pinfunction "DI_4-DIN") (pintype "input"))
      (node (ref "LED13") (pin "2-DOUT") (pinfunction "DO_2-DOUT") (pintype "output"))
    )
    (net (code "45") (name "Net-(LED13-DI)") (class "Default")
      (node (ref "LED13") (pin "4-DIN") (pinfunction "DI_4-DIN") (pintype "input"))
      (node (ref "LED14") (pin "2-DOUT") (pinfunction "DO_2-DOUT") (pintype "output"))
    )
    (net (code "46") (name "Net-(LED14-DI)") (class "Default")
      (node (ref "LED14") (pin "4-DIN") (pinfunction "DI_4-DIN") (pintype "input"))
      (node (ref "LED5") (pin "2-DOUT") (pinfunction "DO_2-DOUT") (pintype "output"))
    )
    (net (code "47") (name "Net-(LED15-DI)") (class "Default")
      (node (ref "LED15") (pin "4-DIN") (pinfunction "DI_4-DIN") (pintype "input"))
      (node (ref "LED24") (pin "2-DOUT") (pinfunction "DO_2-DOUT") (pintype "output"))
    )
    (net (code "48") (name "Net-(LED15-DO)") (class "Default")
      (node (ref "LED15") (pin "2-DOUT") (pinfunction "DO_2-DOUT") (pintype "output"))
      (node (ref "LED26") (pin "4-DIN") (pinfunction "DI_4-DIN") (pintype "input"))
    )
    (net (code "49") (name "Net-(LED16-DI)") (class "Default")
      (node (ref "LED16") (pin "4-DIN") (pinfunction "DI_4-DIN") (pintype "input"))
      (node (ref "LED17") (pin "2-DOUT") (pinfunction "DO_2-DOUT") (pintype "output"))
    )
    (net (code "50") (name "Net-(LED16-DO)") (class "Default")
      (node (ref "LED16") (pin "2-DOUT") (pinfunction "DO_2-DOUT") (pintype "output"))
      (node (ref "LED27") (pin "4-DIN") (pinfunction "DI_4-DIN") (pintype "input"))
    )
    (net (code "51") (name "Net-(LED17-DI)") (class "Default")
      (node (ref "LED17") (pin "4-DIN") (pinfunction "DI_4-DIN") (pintype "input"))
      (node (ref "LED18") (pin "2-DOUT") (pinfunction "DO_2-DOUT") (pintype "output"))
    )
    (net (code "52") (name "Net-(LED18-DI)") (class "Default")
      (node (ref "LED18") (pin "4-DIN") (pinfunction "DI_4-DIN") (pintype "input"))
      (node (ref "LED19") (pin "2-DOUT") (pinfunction "DO_2-DOUT") (pintype "output"))
    )
    (net (code "53") (name "Net-(LED19-DI)") (class "Default")
      (node (ref "LED19") (pin "4-DIN") (pinfunction "DI_4-DIN") (pintype "input"))
      (node (ref "LED25") (pin "2-DOUT") (pinfunction "DO_2-DOUT") (pintype "output"))
    )
    (net (code "54") (name "Net-(LED20-DI)") (class "Default")
      (node (ref "LED20") (pin "4-DIN") (pinfunction "DI_4-DIN") (pintype "input"))
      (node (ref "LED6") (pin "2-DOUT") (pinfunction "DO_2-DOUT") (pintype "output"))
    )
    (net (code "55") (name "Net-(LED20-DO)") (class "Default")
      (node (ref "LED20") (pin "2-DOUT") (pinfunction "DO_2-DOUT") (pintype "output"))
      (node (ref "LED21") (pin "4-DIN") (pinfunction "DI_4-DIN") (pintype "input"))
    )
    (net (code "56") (name "Net-(LED21-DO)") (class "Default")
      (node (ref "LED21") (pin "2-DOUT") (pinfunction "DO_2-DOUT") (pintype "output"))
      (node (ref "LED22") (pin "4-DIN") (pinfunction "DI_4-DIN") (pintype "input"))
    )
    (net (code "57") (name "Net-(LED22-DO)") (class "Default")
      (node (ref "LED22") (pin "2-DOUT") (pinfunction "DO_2-DOUT") (pintype "output"))
      (node (ref "LED23") (pin "4-DIN") (pinfunction "DI_4-DIN") (pintype "input"))
    )
    (net (code "58") (name "Net-(LED23-DO)") (class "Default")
      (node (ref "LED23") (pin "2-DOUT") (pinfunction "DO_2-DOUT") (pintype "output"))
      (node (ref "LED24") (pin "4-DIN") (pinfunction "DI_4-DIN") (pintype "input"))
    )
    (net (code "59") (name "Net-(LED25-DI)") (class "Default")
      (node (ref "LED25") (pin "4-DIN") (pinfunction "DI_4-DIN") (pintype "input"))
      (node (ref "LED45") (pin "2-DOUT") (pinfunction "DO_2-DOUT") (pintype "output"))
    )
    (net (code "60") (name "Net-(LED26-DO)") (class "Default")
      (node (ref "LED26") (pin "2-DOUT") (pinfunction "DO_2-DOUT") (pintype "output"))
      (node (ref "LED32") (pin "4-DIN") (pinfunction "DI_4-DIN") (pintype "input"))
    )
    (net (code "61") (name "Net-(LED27-DO)") (class "Default")
      (node (ref "LED27") (pin "2-DOUT") (pinfunction "DO_2-DOUT") (pintype "output"))
      (node (ref "LED28") (pin "4-DIN") (pinfunction "DI_4-DIN") (pintype "input"))
    )
    (net (code "62") (name "Net-(LED28-DO)") (class "Default")
      (node (ref "LED28") (pin "2-DOUT") (pinfunction "DO_2-DOUT") (pintype "output"))
      (node (ref "LED29") (pin "4-DIN") (pinfunction "DI_4-DIN") (pintype "input"))
    )
    (net (code "63") (name "Net-(LED29-DO)") (class "Default")
      (node (ref "LED29") (pin "2-DOUT") (pinfunction "DO_2-DOUT") (pintype "output"))
      (node (ref "LED30") (pin "4-DIN") (pinfunction "DI_4-DIN") (pintype "input"))
    )
    (net (code "64") (name "Net-(LED30-DO)") (class "Default")
      (node (ref "LED30") (pin "2-DOUT") (pinfunction "DO_2-DOUT") (pintype "output"))
      (node (ref "LED31") (pin "4-DIN") (pinfunction "DI_4-DIN") (pintype "input"))
    )
    (net (code "65") (name "Net-(LED31-DO)") (class "Default")
      (node (ref "LED31") (pin "2-DOUT") (pinfunction "DO_2-DOUT") (pintype "output"))
      (node (ref "LED50") (pin "4-DIN") (pinfunction "DI_4-DIN") (pintype "input"))
    )
    (net (code "66") (name "Net-(LED32-DO)") (class "Default")
      (node (ref "LED32") (pin "2-DOUT") (pinfunction "DO_2-DOUT") (pintype "output"))
      (node (ref "LED38") (pin "4-DIN") (pinfunction "DI_4-DIN") (pintype "input"))
    )
    (net (code "67") (name "Net-(LED33-DI)") (class "Default")
      (node (ref "LED33") (pin "4-DIN") (pinfunction "DI_4-DIN") (pintype "input"))
      (node (ref "LED34") (pin "2-DOUT") (pinfunction "DO_2-DOUT") (pintype "output"))
    )
    (net (code "68") (name "Net-(LED33-DO)") (class "Default")
      (node (ref "LED33") (pin "2-DOUT") (pinfunction "DO_2-DOUT") (pintype "output"))
      (node (ref "LED73") (pin "4-DIN") (pinfunction "DI_4-DIN") (pintype "input"))
    )
    (net (code "69") (name "Net-(LED34-DI)") (class "Default")
      (node (ref "LED34") (pin "4-DIN") (pinfunction "DI_4-DIN") (pintype "input"))
      (node (ref "LED35") (pin "2-DOUT") (pinfunction "DO_2-DOUT") (pintype "output"))
    )
    (net (code "70") (name "Net-(LED35-DI)") (class "Default")
      (node (ref "LED35") (pin "4-DIN") (pinfunction "DI_4-DIN") (pintype "input"))
      (node (ref "LED36") (pin "2-DOUT") (pinfunction "DO_2-DOUT") (pintype "output"))
    )
    (net (code "71") (name "Net-(LED36-DI)") (class "Default")
      (node (ref "LED36") (pin "4-DIN") (pinfunction "DI_4-DIN") (pintype "input"))
      (node (ref "LED37") (pin "2-DOUT") (pinfunction "DO_2-DOUT") (pintype "output"))
    )
    (net (code "72") (name "Net-(LED37-DI)") (class "Default")
      (node (ref "LED37") (pin "4-DIN") (pinfunction "DI_4-DIN") (pintype "input"))
      (node (ref "LED39") (pin "2-DOUT") (pinfunction "DO_2-DOUT") (pintype "output"))
    )
    (net (code "73") (name "Net-(LED38-DO)") (class "Default")
      (node (ref "LED38") (pin "2-DOUT") (pinfunction "DO_2-DOUT") (pintype "output"))
      (node (ref "LED44") (pin "4-DIN") (pinfunction "DI_4-DIN") (pintype "input"))
    )
    (net (code "74") (name "Net-(LED39-DI)") (class "Default")
      (node (ref "LED39") (pin "4-DIN") (pinfunction "DI_4-DIN") (pintype "input"))
      (node (ref "LED40") (pin "2-DOUT") (pinfunction "DO_2-DOUT") (pintype "output"))
    )
    (net (code "75") (name "Net-(LED40-DI)") (class "Default")
      (node (ref "LED40") (pin "4-DIN") (pinfunction "DI_4-DIN") (pintype "input"))
      (node (ref "LED41") (pin "2-DOUT") (pinfunction "DO_2-DOUT") (pintype "output"))
    )
    (net (code "76") (name "Net-(LED41-DI)") (class "Default")
      (node (ref "LED41") (pin "4-DIN") (pinfunction "DI_4-DIN") (pintype "input"))
      (node (ref "LED42") (pin "2-DOUT") (pinfunction "DO_2-DOUT") (pintype "output"))
    )
    (net (code "77") (name "Net-(LED42-DI)") (class "Default")
      (node (ref "LED42") (pin "4-DIN") (pinfunction "DI_4-DIN") (pintype "input"))
      (node (ref "LED43") (pin "2-DOUT") (pinfunction "DO_2-DOUT") (pintype "output"))
    )
    (net (code "78") (name "Net-(LED43-DI)") (class "Default")
      (node (ref "LED43") (pin "4-DIN") (pinfunction "DI_4-DIN") (pintype "input"))
      (node (ref "LED58") (pin "2-DOUT") (pinfunction "DO_2-DOUT") (pintype "output"))
    )
    (net (code "79") (name "Net-(LED44-DO)") (class "Default")
      (node (ref "LED44") (pin "2-DOUT") (pinfunction "DO_2-DOUT") (pintype "output"))
      (node (ref "LED55") (pin "4-DIN") (pinfunction "DI_4-DIN") (pintype "input"))
    )
    (net (code "80") (name "Net-(LED45-DI)") (class "Default")
      (node (ref "LED45") (pin "4-DIN") (pinfunction "DI_4-DIN") (pintype "input"))
      (node (ref "LED46") (pin "2-DOUT") (pinfunction "DO_2-DOUT") (pintype "output"))
    )
    (net (code "81") (name "Net-(LED46-DI)") (class "Default")
      (node (ref "LED46") (pin "4-DIN") (pinfunction "DI_4-DIN") (pintype "input"))
      (node (ref "LED47") (pin "2-DOUT") (pinfunction "DO_2-DOUT") (pintype "output"))
    )
    (net (code "82") (name "Net-(LED47-DI)") (class "Default")
      (node (ref "LED47") (pin "4-DIN") (pinfunction "DI_4-DIN") (pintype "input"))
      (node (ref "LED48") (pin "2-DOUT") (pinfunction "DO_2-DOUT") (pintype "output"))
    )
    (net (code "83") (name "Net-(LED48-DI)") (class "Default")
      (node (ref "LED48") (pin "4-DIN") (pinfunction "DI_4-DIN") (pintype "input"))
      (node (ref "LED49") (pin "2-DOUT") (pinfunction "DO_2-DOUT") (pintype "output"))
    )
    (net (code "84") (name "Net-(LED49-DI)") (class "Default")
      (node (ref "LED49") (pin "4-DIN") (pinfunction "DI_4-DIN") (pintype "input"))
      (node (ref "LED60") (pin "2-DOUT") (pinfunction "DO_2-DOUT") (pintype "output"))
    )
    (net (code "85") (name "Net-(LED50-DO)") (class "Default")
      (node (ref "LED50") (pin "2-DOUT") (pinfunction "DO_2-DOUT") (pintype "output"))
      (node (ref "LED51") (pin "4-DIN") (pinfunction "DI_4-DIN") (pintype "input"))
    )
    (net (code "86") (name "Net-(LED51-DO)") (class "Default")
      (node (ref "LED51") (pin "2-DOUT") (pinfunction "DO_2-DOUT") (pintype "output"))
      (node (ref "LED52") (pin "4-DIN") (pinfunction "DI_4-DIN") (pintype "input"))
    )
    (net (code "87") (name "Net-(LED52-DO)") (class "Default")
      (node (ref "LED52") (pin "2-DOUT") (pinfunction "DO_2-DOUT") (pintype "output"))
      (node (ref "LED53") (pin "4-DIN") (pinfunction "DI_4-DIN") (pintype "input"))
    )
    (net (code "88") (name "Net-(LED53-DO)") (class "Default")
      (node (ref "LED53") (pin "2-DOUT") (pinfunction "DO_2-DOUT") (pintype "output"))
      (node (ref "LED54") (pin "4-DIN") (pinfunction "DI_4-DIN") (pintype "input"))
    )
    (net (code "89") (name "Net-(LED54-DO)") (class "Default")
      (node (ref "LED54") (pin "2-DOUT") (pinfunction "DO_2-DOUT") (pintype "output"))
      (node (ref "LED65") (pin "4-DIN") (pinfunction "DI_4-DIN") (pintype "input"))
    )
    (net (code "90") (name "Net-(LED55-DO)") (class "Default")
      (node (ref "LED55") (pin "2-DOUT") (pinfunction "DO_2-DOUT") (pintype "output"))
      (node (ref "LED56") (pin "4-DIN") (pinfunction "DI_4-DIN") (pintype "input"))
    )
    (net (code "91") (name "Net-(LED56-DO)") (class "Default")
      (node (ref "LED56") (pin "2-DOUT") (pinfunction "DO_2-DOUT") (pintype "output"))
      (node (ref "LED57") (pin "4-DIN") (pinfunction "DI_4-DIN") (pintype "input"))
    )
    (net (code "92") (name "Net-(LED57-DO)") (class "Default")
      (node (ref "LED57") (pin "2-DOUT") (pinfunction "DO_2-DOUT") (pintype "output"))
      (node (ref "LED69") (pin "4-DIN") (pinfunction "DI_4-DIN") (pintype "input"))
    )
    (net (code "93") (name "Net-(LED58-DI)") (class "Default")
      (node (ref "LED58") (pin "4-DIN") (pinfunction "DI_4-DIN") (pintype "input"))
      (node (ref "LED59") (pin "2-DOUT") (pinfunction "DO_2-DOUT") (pintype "output"))
    )
    (net (code "94") (name "Net-(LED59-DI)") (class "Default")
      (node (ref "LED59") (pin "4-DIN") (pinfunction "DI_4-DIN") (pintype "input"))
      (node (ref "LED63") (pin "2-DOUT") (pinfunction "DO_2-DOUT") (pintype "output"))
    )
    (net (code "95") (name "Net-(LED60-DI)") (class "Default")
      (node (ref "LED60") (pin "4-DIN") (pinfunction "DI_4-DIN") (pintype "input"))
      (node (ref "LED61") (pin "2-DOUT") (pinfunction "DO_2-DOUT") (pintype "output"))
    )
    (net (code "96") (name "Net-(LED61-DI)") (class "Default")
      (node (ref "LED61") (pin "4-DIN") (pinfunction "DI_4-DIN") (pintype "input"))
      (node (ref "LED62") (pin "2-DOUT") (pinfunction "DO_2-DOUT") (pintype "output"))
    )
    (net (code "97") (name "Net-(LED62-DI)") (class "Default")
      (node (ref "LED62") (pin "4-DIN") (pinfunction "DI_4-DIN") (pintype "input"))
      (node (ref "LED68") (pin "2-DOUT") (pinfunction "DO_2-DOUT") (pintype "output"))
    )
    (net (code "98") (name "Net-(LED63-DI)") (class "Default")
      (node (ref "LED63") (pin "4-DIN") (pinfunction "DI_4-DIN") (pintype "input"))
      (node (ref "LED64") (pin "2-DOUT") (pinfunction "DO_2-DOUT") (pintype "output"))
    )
    (net (code "99") (name "Net-(LED64-DI)") (class "Default")
      (node (ref "LED64") (pin "4-DIN") (pinfunction "DI_4-DIN") (pintype "input"))
      (node (ref "LED72") (pin "2-DOUT") (pinfunction "DO_2-DOUT") (pintype "output"))
    )
    (net (code "100") (name "Net-(LED65-DO)") (class "Default")
      (node (ref "LED65") (pin "2-DOUT") (pinfunction "DO_2-DOUT") (pintype "output"))
      (node (ref "LED66") (pin "4-DIN") (pinfunction "DI_4-DIN") (pintype "input"))
    )
    (net (code "101") (name "Net-(LED66-DO)") (class "Default")
      (node (ref "LED66") (pin "2-DOUT") (pinfunction "DO_2-DOUT") (pintype "output"))
      (node (ref "LED67") (pin "4-DIN") (pinfunction "DI_4-DIN") (pintype "input"))
    )
    (net (code "102") (name "Net-(LED67-DO)") (class "Default")
      (node (ref "LED67") (pin "2-DOUT") (pinfunction "DO_2-DOUT") (pintype "output"))
      (node (ref "LED70") (pin "4-DIN") (pinfunction "DI_4-DIN") (pintype "input"))
    )
    (net (code "103") (name "Net-(LED68-DI)") (class "Default")
      (node (ref "LED68") (pin "4-DIN") (pinfunction "DI_4-DIN") (pintype "input"))
      (node (ref "LED69") (pin "2-DOUT") (pinfunction "DO_2-DOUT") (pintype "output"))
    )
    (net (code "104") (name "Net-(LED70-DO)") (class "Default")
      (node (ref "LED70") (pin "2-DOUT") (pinfunction "DO_2-DOUT") (pintype "output"))
      (node (ref "LED71") (pin "4-DIN") (pinfunction "DI_4-DIN") (pintype "input"))
    )
    (net (code "105") (name "Net-(LED71-DO)") (class "Default")
      (node (ref "LED71") (pin "2-DOUT") (pinfunction "DO_2-DOUT") (pintype "output"))
      (node (ref "LED72") (pin "4-DIN") (pinfunction "DI_4-DIN") (pintype "input"))
    )
    (net (code "106") (name "Net-(LED73-DO)") (class "Default")
      (node (ref "LED73") (pin "2-DOUT") (pinfunction "DO_2-DOUT") (pintype "output"))
      (node (ref "LED74") (pin "4-DIN") (pinfunction "DI_4-DIN") (pintype "input"))
    )
    (net (code "107") (name "Net-(LED74-DO)") (class "Default")
      (node (ref "LED74") (pin "2-DOUT") (pinfunction "DO_2-DOUT") (pintype "output"))
      (node (ref "LED75") (pin "4-DIN") (pinfunction "DI_4-DIN") (pintype "input"))
    )
    (net (code "108") (name "Net-(LED75-DO)") (class "Default")
      (node (ref "LED75") (pin "2-DOUT") (pinfunction "DO_2-DOUT") (pintype "output"))
      (node (ref "LED76") (pin "4-DIN") (pinfunction "DI_4-DIN") (pintype "input"))
    )
    (net (code "109") (name "Net-(LED76-DO)") (class "Default")
      (node (ref "LED76") (pin "2-DOUT") (pinfunction "DO_2-DOUT") (pintype "output"))
      (node (ref "LED77") (pin "4-DIN") (pinfunction "DI_4-DIN") (pintype "input"))
    )
    (net (code "110") (name "Net-(LED77-DO)") (class "Default")
      (node (ref "LED77") (pin "2-DOUT") (pinfunction "DO_2-DOUT") (pintype "output"))
      (node (ref "LED78") (pin "4-DIN") (pinfunction "DI_4-DIN") (pintype "input"))
    )
    (net (code "111") (name "Net-(LED78-DO)") (class "Default")
      (node (ref "LED78") (pin "2-DOUT") (pinfunction "DO_2-DOUT") (pintype "output"))
      (node (ref "LED79") (pin "4-DIN") (pinfunction "DI_4-DIN") (pintype "input"))
    )
    (net (code "112") (name "Net-(LED79-DO)") (class "Default")
      (node (ref "LED79") (pin "2-DOUT") (pinfunction "DO_2-DOUT") (pintype "output"))
      (node (ref "LED80") (pin "4-DIN") (pinfunction "DI_4-DIN") (pintype "input"))
    )
    (net (code "113") (name "Net-(LED80-DO)") (class "Default")
      (node (ref "LED80") (pin "2-DOUT") (pinfunction "DO_2-DOUT") (pintype "output"))
      (node (ref "LED81") (pin "4-DIN") (pinfunction "DI_4-DIN") (pintype "input"))
    )
    (net (code "114") (name "Net-(LED81-DO)") (class "Default")
      (node (ref "LED81") (pin "2-DOUT") (pinfunction "DO_2-DOUT") (pintype "output"))
      (node (ref "LED82") (pin "4-DIN") (pinfunction "DI_4-DIN") (pintype "input"))
    )
    (net (code "115") (name "Net-(LED82-DO)") (class "Default")
      (node (ref "LED82") (pin "2-DOUT") (pinfunction "DO_2-DOUT") (pintype "output"))
      (node (ref "LED83") (pin "4-DIN") (pinfunction "DI_4-DIN") (pintype "input"))
    )
    (net (code "116") (name "Net-(LED83-DO)") (class "Default")
      (node (ref "LED83") (pin "2-DOUT") (pinfunction "DO_2-DOUT") (pintype "output"))
      (node (ref "LED84") (pin "4-DIN") (pinfunction "DI_4-DIN") (pintype "input"))
    )
    (net (code "117") (name "Net-(LED84-DO)") (class "Default")
      (node (ref "LED84") (pin "2-DOUT") (pinfunction "DO_2-DOUT") (pintype "output"))
      (node (ref "LED85") (pin "4-DIN") (pinfunction "DI_4-DIN") (pintype "input"))
    )
    (net (code "118") (name "Net-(LED85-DO)") (class "Default")
      (node (ref "LED85") (pin "2-DOUT") (pinfunction "DO_2-DOUT") (pintype "output"))
      (node (ref "LED94") (pin "4-DIN") (pinfunction "DI_4-DIN") (pintype "input"))
    )
    (net (code "119") (name "Net-(LED86-DI)") (class "Default")
      (node (ref "LED86") (pin "4-DIN") (pinfunction "DI_4-DIN") (pintype "input"))
      (node (ref "LED87") (pin "2-DOUT") (pinfunction "DO_2-DOUT") (pintype "output"))
    )
    (net (code "120") (name "Net-(LED86-DO)") (class "Default")
      (node (ref "LED86") (pin "2-DOUT") (pinfunction "DO_2-DOUT") (pintype "output"))
      (node (ref "LED95") (pin "4-DIN") (pinfunction "DI_4-DIN") (pintype "input"))
    )
    (net (code "121") (name "Net-(LED87-DI)") (class "Default")
      (node (ref "LED87") (pin "4-DIN") (pinfunction "DI_4-DIN") (pintype "input"))
      (node (ref "LED88") (pin "2-DOUT") (pinfunction "DO_2-DOUT") (pintype "output"))
    )
    (net (code "122") (name "Net-(LED88-DI)") (class "Default")
      (node (ref "LED88") (pin "4-DIN") (pinfunction "DI_4-DIN") (pintype "input"))
      (node (ref "LED89") (pin "2-DOUT") (pinfunction "DO_2-DOUT") (pintype "output"))
    )
    (net (code "123") (name "Net-(LED89-DI)") (class "Default")
      (node (ref "LED89") (pin "4-DIN") (pinfunction "DI_4-DIN") (pintype "input"))
      (node (ref "LED90") (pin "2-DOUT") (pinfunction "DO_2-DOUT") (pintype "output"))
    )
    (net (code "124") (name "Net-(LED90-DI)") (class "Default")
      (node (ref "LED90") (pin "4-DIN") (pinfunction "DI_4-DIN") (pintype "input"))
      (node (ref "LED91") (pin "2-DOUT") (pinfunction "DO_2-DOUT") (pintype "output"))
    )
    (net (code "125") (name "Net-(LED91-DI)") (class "Default")
      (node (ref "LED91") (pin "4-DIN") (pinfunction "DI_4-DIN") (pintype "input"))
      (node (ref "LED92") (pin "2-DOUT") (pinfunction "DO_2-DOUT") (pintype "output"))
    )
    (net (code "126") (name "Net-(LED92-DI)") (class "Default")
      (node (ref "LED92") (pin "4-DIN") (pinfunction "DI_4-DIN") (pintype "input"))
      (node (ref "LED93") (pin "2-DOUT") (pinfunction "DO_2-DOUT") (pintype "output"))
    )
    (net (code "127") (name "Net-(LED93-DI)") (class "Default")
      (node (ref "LED93") (pin "4-DIN") (pinfunction "DI_4-DIN") (pintype "input"))
      (node (ref "LED94") (pin "2-DOUT") (pinfunction "DO_2-DOUT") (pintype "output"))
    )
    (net (code "128") (name "Net-(LED95-DO)") (class "Default")
      (node (ref "LED95") (pin "2-DOUT") (pinfunction "DO_2-DOUT") (pintype "output"))
      (node (ref "LED96") (pin "4-DIN") (pinfunction "DI_4-DIN") (pintype "input"))
    )
    (net (code "129") (name "Net-(LED96-DO)") (class "Default")
      (node (ref "LED96") (pin "2-DOUT") (pinfunction "DO_2-DOUT") (pintype "output"))
      (node (ref "LED97") (pin "4-DIN") (pinfunction "DI_4-DIN") (pintype "input"))
    )
    (net (code "130") (name "Net-(LED97-DO)") (class "Default")
      (node (ref "LED97") (pin "2-DOUT") (pinfunction "DO_2-DOUT") (pintype "output"))
      (node (ref "LED98") (pin "4-DIN") (pinfunction "DI_4-DIN") (pintype "input"))
    )
    (net (code "131") (name "Net-(LED98-DO)") (class "Default")
      (node (ref "LED98") (pin "2-DOUT") (pinfunction "DO_2-DOUT") (pintype "output"))
      (node (ref "LED99") (pin "4-DIN") (pinfunction "DI_4-DIN") (pintype "input"))
    )
    (net (code "132") (name "Net-(SR-S)") (class "Default")
      (node (ref "R6") (pin "1") (pinfunction "1_1") (pintype "passive"))
      (node (ref "SR") (pin "1") (pinfunction "S_1") (pintype "passive"))
      (node (ref "SR") (pin "2") (pinfunction "S1_2") (pintype "passive"))
      (node (ref "U2") (pin "3") (pinfunction "EN_3") (pintype "input"))
    )
    (net (code "133") (name "Net-(U1-VCC1)") (class "Default")
      (node (ref "BT1") (pin "P") (pinfunction "P_P") (pintype "passive"))
      (node (ref "U1") (pin "8") (pinfunction "VCC1_8") (pintype "power_in"))
    )
    (net (code "134") (name "Net-(U1-X1)") (class "Default")
      (node (ref "U1") (pin "2") (pinfunction "X1_2") (pintype "input"))
      (node (ref "Y1") (pin "1") (pinfunction "1_1") (pintype "passive"))
    )
    (net (code "135") (name "Net-(U1-X2)") (class "Default")
      (node (ref "U1") (pin "3") (pinfunction "X2_3") (pintype "output"))
      (node (ref "Y1") (pin "2") (pinfunction "2_2") (pintype "passive"))
    )
    (net (code "136") (name "Net-(U2-IO19)") (class "Default")
      (node (ref "R3") (pin "1") (pinfunction "1_1") (pintype "passive"))
      (node (ref "U2") (pin "13") (pinfunction "IO19_13") (pintype "bidirectional"))
    )
    (net (code "137") (name "Net-(U2-IO20)") (class "Default")
      (node (ref "R4") (pin "1") (pinfunction "1_1") (pintype "passive"))
      (node (ref "U2") (pin "14") (pinfunction "IO20_14") (pintype "bidirectional"))
    )
    (net (code "138") (name "Y_POWER-SIM_3.3V") (class "Default")
      (node (ref "C12") (pin "2") (pinfunction "2_2") (pintype "passive"))
      (node (ref "C15") (pin "2") (pinfunction "2_2") (pintype "passive"))
      (node (ref "C19") (pin "2") (pinfunction "2_2") (pintype "passive"))
      (node (ref "C42") (pin "2") (pinfunction "2_2") (pintype "passive"))
      (node (ref "C43") (pin "2") (pinfunction "2_2") (pintype "passive"))
      (node (ref "J1") (pin "4") (pinfunction "VDD_4") (pintype "power_in"))
      (node (ref "R1") (pin "2") (pinfunction "2_2") (pintype "passive"))
      (node (ref "R10") (pin "2") (pinfunction "2_2") (pintype "passive"))
      (node (ref "R11") (pin "2") (pinfunction "2_2") (pintype "passive"))
      (node (ref "R12") (pin "2") (pinfunction "2_2") (pintype "passive"))
      (node (ref "R13") (pin "2") (pinfunction "2_2") (pintype "passive"))
      (node (ref "R14") (pin "2") (pinfunction "2_2") (pintype "passive"))
      (node (ref "R15") (pin "1") (pinfunction "1_1") (pintype "passive"))
      (node (ref "R2") (pin "2") (pinfunction "2_2") (pintype "passive"))
      (node (ref "R5") (pin "2") (pinfunction "2_2") (pintype "passive"))
      (node (ref "R6") (pin "2") (pinfunction "2_2") (pintype "passive"))
      (node (ref "R7") (pin "1") (pinfunction "1_1") (pintype "passive"))
      (node (ref "R8") (pin "2") (pinfunction "2_2") (pintype "passive"))
      (node (ref "R9") (pin "2") (pinfunction "2_2") (pintype "passive"))
      (node (ref "U$1") (pin "P$1") (pinfunction "P$1_P$1") (pintype "bidirectional"))
      (node (ref "U2") (pin "2") (pinfunction "3V3_2") (pintype "power_in"))
      (node (ref "VR1") (pin "3") (pinfunction "OUTPUT_3") (pintype "output"))
    )
    (net (code "139") (name "Y_POWER-SIM_5V") (class "Default")
      (node (ref "C1") (pin "1") (pinfunction "1_1") (pintype "passive"))
      (node (ref "C10") (pin "1") (pinfunction "1_1") (pintype "passive"))
      (node (ref "C100") (pin "1") (pinfunction "1_1") (pintype "passive"))
      (node (ref "C101") (pin "1") (pinfunction "1_1") (pintype "passive"))
      (node (ref "C102") (pin "1") (pinfunction "1_1") (pintype "passive"))
      (node (ref "C103") (pin "1") (pinfunction "1_1") (pintype "passive"))
      (node (ref "C104") (pin "1") (pinfunction "1_1") (pintype "passive"))
      (node (ref "C105") (pin "1") (pinfunction "1_1") (pintype "passive"))
      (node (ref "C106") (pin "1") (pinfunction "1_1") (pintype "passive"))
      (node (ref "C107") (pin "1") (pinfunction "1_1") (pintype "passive"))
      (node (ref "C108") (pin "1") (pinfunction "1_1") (pintype "passive"))
      (node (ref "C109") (pin "1") (pinfunction "1_1") (pintype "passive"))
      (node (ref "C11") (pin "1") (pinfunction "1_1") (pintype "passive"))
      (node (ref "C13") (pin "2") (pinfunction "2_2") (pintype "passive"))
      (node (ref "C16") (pin "2") (pinfunction "2_2") (pintype "passive"))
      (node (ref "C2") (pin "1") (pinfunction "1_1") (pintype "passive"))
      (node (ref "C20") (pin "1") (pinfunction "1_1") (pintype "passive"))
      (node (ref "C21") (pin "1") (pinfunction "1_1") (pintype "passive"))
      (node (ref "C22") (pin "1") (pinfunction "1_1") (pintype "passive"))
      (node (ref "C23") (pin "1") (pinfunction "1_1") (pintype "passive"))
      (node (ref "C24") (pin "1") (pinfunction "1_1") (pintype "passive"))
      (node (ref "C25") (pin "1") (pinfunction "1_1") (pintype "passive"))
      (node (ref "C26") (pin "1") (pinfunction "1_1") (pintype "passive"))
      (node (ref "C27") (pin "1") (pinfunction "1_1") (pintype "passive"))
      (node (ref "C28") (pin "1") (pinfunction "1_1") (pintype "passive"))
      (node (ref "C29") (pin "1") (pinfunction "1_1") (pintype "passive"))
      (node (ref "C3") (pin "1") (pinfunction "1_1") (pintype "passive"))
      (node (ref "C30") (pin "1") (pinfunction "1_1") (pintype "passive"))
      (node (ref "C31") (pin "1") (pinfunction "1_1") (pintype "passive"))
      (node (ref "C32") (pin "1") (pinfunction "1_1") (pintype "passive"))
      (node (ref "C33") (pin "1") (pinfunction "1_1") (pintype "passive"))
      (node (ref "C34") (pin "1") (pinfunction "1_1") (pintype "passive"))
      (node (ref "C35") (pin "1") (pinfunction "1_1") (pintype "passive"))
      (node (ref "C36") (pin "1") (pinfunction "1_1") (pintype "passive"))
      (node (ref "C37") (pin "1") (pinfunction "1_1") (pintype "passive"))
      (node (ref "C38") (pin "1") (pinfunction "1_1") (pintype "passive"))
      (node (ref "C39") (pin "1") (pinfunction "1_1") (pintype "passive"))
      (node (ref "C4") (pin "1") (pinfunction "1_1") (pintype "passive"))
      (node (ref "C40") (pin "1") (pinfunction "1_1") (pintype "passive"))
      (node (ref "C41") (pin "1") (pinfunction "1_1") (pintype "passive"))
      (node (ref "C44") (pin "1") (pinfunction "1_1") (pintype "passive"))
      (node (ref "C45") (pin "1") (pinfunction "1_1") (pintype "passive"))
      (node (ref "C46") (pin "1") (pinfunction "1_1") (pintype "passive"))
      (node (ref "C47") (pin "1") (pinfunction "1_1") (pintype "passive"))
      (node (ref "C48") (pin "1") (pinfunction "1_1") (pintype "passive"))
      (node (ref "C49") (pin "1") (pinfunction "1_1") (pintype "passive"))
      (node (ref "C5") (pin "1") (pinfunction "1_1") (pintype "passive"))
      (node (ref "C50") (pin "1") (pinfunction "1_1") (pintype "passive"))
      (node (ref "C51") (pin "1") (pinfunction "1_1") (pintype "passive"))
      (node (ref "C52") (pin "1") (pinfunction "1_1") (pintype "passive"))
      (node (ref "C53") (pin "1") (pinfunction "1_1") (pintype "passive"))
      (node (ref "C54") (pin "1") (pinfunction "1_1") (pintype "passive"))
      (node (ref "C55") (pin "1") (pinfunction "1_1") (pintype "passive"))
      (node (ref "C56") (pin "1") (pinfunction "1_1") (pintype "passive"))
      (node (ref "C57") (pin "1") (pinfunction "1_1") (pintype "passive"))
      (node (ref "C58") (pin "1") (pinfunction "1_1") (pintype "passive"))
      (node (ref "C59") (pin "1") (pinfunction "1_1") (pintype "passive"))
      (node (ref "C6") (pin "1") (pinfunction "1_1") (pintype "passive"))
      (node (ref "C60") (pin "1") (pinfunction "1_1") (pintype "passive"))
      (node (ref "C61") (pin "1") (pinfunction "1_1") (pintype "passive"))
      (node (ref "C62") (pin "1") (pinfunction "1_1") (pintype "passive"))
      (node (ref "C63") (pin "1") (pinfunction "1_1") (pintype "passive"))
      (node (ref "C64") (pin "1") (pinfunction "1_1") (pintype "passive"))
      (node (ref "C65") (pin "1") (pinfunction "1_1") (pintype "passive"))
      (node (ref "C66") (pin "1") (pinfunction "1_1") (pintype "passive"))
      (node (ref "C67") (pin "1") (pinfunction "1_1") (pintype "passive"))
      (node (ref "C68") (pin "1") (pinfunction "1_1") (pintype "passive"))
      (node (ref "C69") (pin "1") (pinfunction "1_1") (pintype "passive"))
      (node (ref "C7") (pin "1") (pinfunction "1_1") (pintype "passive"))
      (node (ref "C70") (pin "1") (pinfunction "1_1") (pintype "passive"))
      (node (ref "C71") (pin "1") (pinfunction "1_1") (pintype "passive"))
      (node (ref "C72") (pin "1") (pinfunction "1_1") (pintype "passive"))
      (node (ref "C73") (pin "1") (pinfunction "1_1") (pintype "passive"))
      (node (ref "C74") (pin "1") (pinfunction "1_1") (pintype "passive"))
      (node (ref "C75") (pin "1") (pinfunction "1_1") (pintype "passive"))
      (node (ref "C76") (pin "1") (pinfunction "1_1") (pintype "passive"))
      (node (ref "C77") (pin "1") (pinfunction "1_1") (pintype "passive"))
      (node (ref "C78") (pin "1") (pinfunction "1_1") (pintype "passive"))
      (node (ref "C79") (pin "1") (pinfunction "1_1") (pintype "passive"))
      (node (ref "C8") (pin "1") (pinfunction "1_1") (pintype "passive"))
      (node (ref "C80") (pin "1") (pinfunction "1_1") (pintype "passive"))
      (node (ref "C81") (pin "1") (pinfunction "1_1") (pintype "passive"))
      (node (ref "C82") (pin "1") (pinfunction "1_1") (pintype "passive"))
      (node (ref "C83") (pin "1") (pinfunction "1_1") (pintype "passive"))
      (node (ref "C84") (pin "1") (pinfunction "1_1") (pintype "passive"))
      (node (ref "C85") (pin "1") (pinfunction "1_1") (pintype "passive"))
      (node (ref "C86") (pin "1") (pinfunction "1_1") (pintype "passive"))
      (node (ref "C87") (pin "1") (pinfunction "1_1") (pintype "passive"))
      (node (ref "C88") (pin "1") (pinfunction "1_1") (pintype "passive"))
      (node (ref "C89") (pin "1") (pinfunction "1_1") (pintype "passive"))
      (node (ref "C9") (pin "1") (pinfunction "1_1") (pintype "passive"))
      (node (ref "C90") (pin "1") (pinfunction "1_1") (pintype "passive"))
      (node (ref "C91") (pin "1") (pinfunction "1_1") (pintype "passive"))
      (node (ref "C92") (pin "1") (pinfunction "1_1") (pintype "passive"))
      (node (ref "C93") (pin "1") (pinfunction "1_1") (pintype "passive"))
      (node (ref "C94") (pin "1") (pinfunction "1_1") (pintype "passive"))
      (node (ref "C95") (pin "1") (pinfunction "1_1") (pintype "passive"))
      (node (ref "C96") (pin "1") (pinfunction "1_1") (pintype "passive"))
      (node (ref "C97") (pin "1") (pinfunction "1_1") (pintype "passive"))
      (node (ref "C98") (pin "1") (pinfunction "1_1") (pintype "passive"))
      (node (ref "C99") (pin "1") (pinfunction "1_1") (pintype "passive"))
      (node (ref "J2") (pin "A4_B9") (pinfunction "VBUS_A4_B9") (pintype "passive"))
      (node (ref "J2") (pin "A9_B4") (pinfunction "VBUS_A9_B4") (pintype "passive"))
      (node (ref "LED1") (pin "1-VDD") (pinfunction "VDD_1-VDD") (pintype "power_in"))
      (node (ref "LED10") (pin "1-VDD") (pinfunction "VDD_1-VDD") (pintype "power_in"))
      (node (ref "LED11") (pin "1-VDD") (pinfunction "VDD_1-VDD") (pintype "power_in"))
      (node (ref "LED12") (pin "1-VDD") (pinfunction "VDD_1-VDD") (pintype "power_in"))
      (node (ref "LED13") (pin "1-VDD") (pinfunction "VDD_1-VDD") (pintype "power_in"))
      (node (ref "LED14") (pin "1-VDD") (pinfunction "VDD_1-VDD") (pintype "power_in"))
      (node (ref "LED15") (pin "1-VDD") (pinfunction "VDD_1-VDD") (pintype "power_in"))
      (node (ref "LED16") (pin "1-VDD") (pinfunction "VDD_1-VDD") (pintype "power_in"))
      (node (ref "LED17") (pin "1-VDD") (pinfunction "VDD_1-VDD") (pintype "power_in"))
      (node (ref "LED18") (pin "1-VDD") (pinfunction "VDD_1-VDD") (pintype "power_in"))
      (node (ref "LED19") (pin "1-VDD") (pinfunction "VDD_1-VDD") (pintype "power_in"))
      (node (ref "LED2") (pin "1-VDD") (pinfunction "VDD_1-VDD") (pintype "power_in"))
      (node (ref "LED20") (pin "1-VDD") (pinfunction "VDD_1-VDD") (pintype "power_in"))
      (node (ref "LED21") (pin "1-VDD") (pinfunction "VDD_1-VDD") (pintype "power_in"))
      (node (ref "LED22") (pin "1-VDD") (pinfunction "VDD_1-VDD") (pintype "power_in"))
      (node (ref "LED23") (pin "1-VDD") (pinfunction "VDD_1-VDD") (pintype "power_in"))
      (node (ref "LED24") (pin "1-VDD") (pinfunction "VDD_1-VDD") (pintype "power_in"))
      (node (ref "LED25") (pin "1-VDD") (pinfunction "VDD_1-VDD") (pintype "power_in"))
      (node (ref "LED26") (pin "1-VDD") (pinfunction "VDD_1-VDD") (pintype "power_in"))
      (node (ref "LED27") (pin "1-VDD") (pinfunction "VDD_1-VDD") (pintype "power_in"))
      (node (ref "LED28") (pin "1-VDD") (pinfunction "VDD_1-VDD") (pintype "power_in"))
      (node (ref "LED29") (pin "1-VDD") (pinfunction "VDD_1-VDD") (pintype "power_in"))
      (node (ref "LED3") (pin "1-VDD") (pinfunction "VDD_1-VDD") (pintype "power_in"))
      (node (ref "LED30") (pin "1-VDD") (pinfunction "VDD_1-VDD") (pintype "power_in"))
      (node (ref "LED31") (pin "1-VDD") (pinfunction "VDD_1-VDD") (pintype "power_in"))
      (node (ref "LED32") (pin "1-VDD") (pinfunction "VDD_1-VDD") (pintype "power_in"))
      (node (ref "LED33") (pin "1-VDD") (pinfunction "VDD_1-VDD") (pintype "power_in"))
      (node (ref "LED34") (pin "1-VDD") (pinfunction "VDD_1-VDD") (pintype "power_in"))
      (node (ref "LED35") (pin "1-VDD") (pinfunction "VDD_1-VDD") (pintype "power_in"))
      (node (ref "LED36") (pin "1-VDD") (pinfunction "VDD_1-VDD") (pintype "power_in"))
      (node (ref "LED37") (pin "1-VDD") (pinfunction "VDD_1-VDD") (pintype "power_in"))
      (node (ref "LED38") (pin "1-VDD") (pinfunction "VDD_1-VDD") (pintype "power_in"))
      (node (ref "LED39") (pin "1-VDD") (pinfunction "VDD_1-VDD") (pintype "power_in"))
      (node (ref "LED4") (pin "1-VDD") (pinfunction "VDD_1-VDD") (pintype "power_in"))
      (node (ref "LED40") (pin "1-VDD") (pinfunction "VDD_1-VDD") (pintype "power_in"))
      (node (ref "LED41") (pin "1-VDD") (pinfunction "VDD_1-VDD") (pintype "power_in"))
      (node (ref "LED42") (pin "1-VDD") (pinfunction "VDD_1-VDD") (pintype "power_in"))
      (node (ref "LED43") (pin "1-VDD") (pinfunction "VDD_1-VDD") (pintype "power_in"))
      (node (ref "LED44") (pin "1-VDD") (pinfunction "VDD_1-VDD") (pintype "power_in"))
      (node (ref "LED45") (pin "1-VDD") (pinfunction "VDD_1-VDD") (pintype "power_in"))
      (node (ref "LED46") (pin "1-VDD") (pinfunction "VDD_1-VDD") (pintype "power_in"))
      (node (ref "LED47") (pin "1-VDD") (pinfunction "VDD_1-VDD") (pintype "power_in"))
      (node (ref "LED48") (pin "1-VDD") (pinfunction "VDD_1-VDD") (pintype "power_in"))
      (node (ref "LED49") (pin "1-VDD") (pinfunction "VDD_1-VDD") (pintype "power_in"))
      (node (ref "LED5") (pin "1-VDD") (pinfunction "VDD_1-VDD") (pintype "power_in"))
      (node (ref "LED50") (pin "1-VDD") (pinfunction "VDD_1-VDD") (pintype "power_in"))
      (node (ref "LED51") (pin "1-VDD") (pinfunction "VDD_1-VDD") (pintype "power_in"))
      (node (ref "LED52") (pin "1-VDD") (pinfunction "VDD_1-VDD") (pintype "power_in"))
      (node (ref "LED53") (pin "1-VDD") (pinfunction "VDD_1-VDD") (pintype "power_in"))
      (node (ref "LED54") (pin "1-VDD") (pinfunction "VDD_1-VDD") (pintype "power_in"))
      (node (ref "LED55") (pin "1-VDD") (pinfunction "VDD_1-VDD") (pintype "power_in"))
      (node (ref "LED56") (pin "1-VDD") (pinfunction "VDD_1-VDD") (pintype "power_in"))
      (node (ref "LED57") (pin "1-VDD") (pinfunction "VDD_1-VDD") (pintype "power_in"))
      (node (ref "LED58") (pin "1-VDD") (pinfunction "VDD_1-VDD") (pintype "power_in"))
      (node (ref "LED59") (pin "1-VDD") (pinfunction "VDD_1-VDD") (pintype "power_in"))
      (node (ref "LED6") (pin "1-VDD") (pinfunction "VDD_1-VDD") (pintype "power_in"))
      (node (ref "LED60") (pin "1-VDD") (pinfunction "VDD_1-VDD") (pintype "power_in"))
      (node (ref "LED61") (pin "1-VDD") (pinfunction "VDD_1-VDD") (pintype "power_in"))
      (node (ref "LED62") (pin "1-VDD") (pinfunction "VDD_1-VDD") (pintype "power_in"))
      (node (ref "LED63") (pin "1-VDD") (pinfunction "VDD_1-VDD") (pintype "power_in"))
      (node (ref "LED64") (pin "1-VDD") (pinfunction "VDD_1-VDD") (pintype "power_in"))
      (node (ref "LED65") (pin "1-VDD") (pinfunction "VDD_1-VDD") (pintype "power_in"))
      (node (ref "LED66") (pin "1-VDD") (pinfunction "VDD_1-VDD") (pintype "power_in"))
      (node (ref "LED67") (pin "1-VDD") (pinfunction "VDD_1-VDD") (pintype "power_in"))
      (node (ref "LED68") (pin "1-VDD") (pinfunction "VDD_1-VDD") (pintype "power_in"))
      (node (ref "LED69") (pin "1-VDD") (pinfunction "VDD_1-VDD") (pintype "power_in"))
      (node (ref "LED7") (pin "1-VDD") (pinfunction "VDD_1-VDD") (pintype "power_in"))
      (node (ref "LED70") (pin "1-VDD") (pinfunction "VDD_1-VDD") (pintype "power_in"))
      (node (ref "LED71") (pin "1-VDD") (pinfunction "VDD_1-VDD") (pintype "power_in"))
      (node (ref "LED72") (pin "1-VDD") (pinfunction "VDD_1-VDD") (pintype "power_in"))
      (node (ref "LED73") (pin "1-VDD") (pinfunction "VDD_1-VDD") (pintype "power_in"))
      (node (ref "LED74") (pin "1-VDD") (pinfunction "VDD_1-VDD") (pintype "power_in"))
      (node (ref "LED75") (pin "1-VDD") (pinfunction "VDD_1-VDD") (pintype "power_in"))
      (node (ref "LED76") (pin "1-VDD") (pinfunction "VDD_1-VDD") (pintype "power_in"))
      (node (ref "LED77") (pin "1-VDD") (pinfunction "VDD_1-VDD") (pintype "power_in"))
      (node (ref "LED78") (pin "1-VDD") (pinfunction "VDD_1-VDD") (pintype "power_in"))
      (node (ref "LED79") (pin "1-VDD") (pinfunction "VDD_1-VDD") (pintype "power_in"))
      (node (ref "LED8") (pin "1-VDD") (pinfunction "VDD_1-VDD") (pintype "power_in"))
      (node (ref "LED80") (pin "1-VDD") (pinfunction "VDD_1-VDD") (pintype "power_in"))
      (node (ref "LED81") (pin "1-VDD") (pinfunction "VDD_1-VDD") (pintype "power_in"))
      (node (ref "LED82") (pin "1-VDD") (pinfunction "VDD_1-VDD") (pintype "power_in"))
      (node (ref "LED83") (pin "1-VDD") (pinfunction "VDD_1-VDD") (pintype "power_in"))
      (node (ref "LED84") (pin "1-VDD") (pinfunction "VDD_1-VDD") (pintype "power_in"))
      (node (ref "LED85") (pin "1-VDD") (pinfunction "VDD_1-VDD") (pintype "power_in"))
      (node (ref "LED86") (pin "1-VDD") (pinfunction "VDD_1-VDD") (pintype "power_in"))
      (node (ref "LED87") (pin "1-VDD") (pinfunction "VDD_1-VDD") (pintype "power_in"))
      (node (ref "LED88") (pin "1-VDD") (pinfunction "VDD_1-VDD") (pintype "power_in"))
      (node (ref "LED89") (pin "1-VDD") (pinfunction "VDD_1-VDD") (pintype "power_in"))
      (node (ref "LED9") (pin "1-VDD") (pinfunction "VDD_1-VDD") (pintype "power_in"))
      (node (ref "LED90") (pin "1-VDD") (pinfunction "VDD_1-VDD") (pintype "power_in"))
      (node (ref "LED91") (pin "1-VDD") (pinfunction "VDD_1-VDD") (pintype "power_in"))
      (node (ref "LED92") (pin "1-VDD") (pinfunction "VDD_1-VDD") (pintype "power_in"))
      (node (ref "LED93") (pin "1-VDD") (pinfunction "VDD_1-VDD") (pintype "power_in"))
      (node (ref "LED94") (pin "1-VDD") (pinfunction "VDD_1-VDD") (pintype "power_in"))
      (node (ref "LED95") (pin "1-VDD") (pinfunction "VDD_1-VDD") (pintype "power_in"))
      (node (ref "LED96") (pin "1-VDD") (pinfunction "VDD_1-VDD") (pintype "power_in"))
      (node (ref "LED97") (pin "1-VDD") (pinfunction "VDD_1-VDD") (pintype "power_in"))
      (node (ref "LED98") (pin "1-VDD") (pinfunction "VDD_1-VDD") (pintype "power_in"))
      (node (ref "LED99") (pin "1-VDD") (pinfunction "VDD_1-VDD") (pintype "power_in"))
      (node (ref "U$3") (pin "P$1") (pinfunction "P$1_P$1") (pintype "bidirectional"))
      (node (ref "U1") (pin "1") (pinfunction "VCC2_1") (pintype "power_in"))
      (node (ref "VR1") (pin "1") (pinfunction "INPUT_1") (pintype "input"))
    )
    (net (code "140") (name "Y_POWER-SIM_GND") (class "Default")
      (node (ref "BT1") (pin "N") (pinfunction "N_N") (pintype "passive"))
      (node (ref "C1") (pin "2") (pinfunction "2_2") (pintype "passive"))
      (node (ref "C10") (pin "2") (pinfunction "2_2") (pintype "passive"))
      (node (ref "C100") (pin "2") (pinfunction "2_2") (pintype "passive"))
      (node (ref "C101") (pin "2") (pinfunction "2_2") (pintype "passive"))
      (node (ref "C102") (pin "2") (pinfunction "2_2") (pintype "passive"))
      (node (ref "C103") (pin "2") (pinfunction "2_2") (pintype "passive"))
      (node (ref "C104") (pin "2") (pinfunction "2_2") (pintype "passive"))
      (node (ref "C105") (pin "2") (pinfunction "2_2") (pintype "passive"))
      (node (ref "C106") (pin "2") (pinfunction "2_2") (pintype "passive"))
      (node (ref "C107") (pin "2") (pinfunction "2_2") (pintype "passive"))
      (node (ref "C108") (pin "2") (pinfunction "2_2") (pintype "passive"))
      (node (ref "C109") (pin "2") (pinfunction "2_2") (pintype "passive"))
      (node (ref "C11") (pin "2") (pinfunction "2_2") (pintype "passive"))
      (node (ref "C110") (pin "1") (pinfunction "1_1") (pintype "passive"))
      (node (ref "C111") (pin "1") (pinfunction "1_1") (pintype "passive"))
      (node (ref "C112") (pin "1") (pinfunction "1_1") (pintype "passive"))
      (node (ref "C113") (pin "1") (pinfunction "1_1") (pintype "passive"))
      (node (ref "C114") (pin "1") (pinfunction "1_1") (pintype "passive"))
      (node (ref "C115") (pin "1") (pinfunction "1_1") (pintype "passive"))
      (node (ref "C12") (pin "1") (pinfunction "1_1") (pintype "passive"))
      (node (ref "C13") (pin "1") (pinfunction "1_1") (pintype "passive"))
      (node (ref "C14") (pin "1") (pinfunction "1_1") (pintype "passive"))
      (node (ref "C15") (pin "1") (pinfunction "1_1") (pintype "passive"))
      (node (ref "C16") (pin "1") (pinfunction "1_1") (pintype "passive"))
      (node (ref "C17") (pin "1") (pinfunction "1_1") (pintype "passive"))
      (node (ref "C18") (pin "1") (pinfunction "1_1") (pintype "passive"))
      (node (ref "C19") (pin "1") (pinfunction "1_1") (pintype "passive"))
      (node (ref "C2") (pin "2") (pinfunction "2_2") (pintype "passive"))
      (node (ref "C20") (pin "2") (pinfunction "2_2") (pintype "passive"))
      (node (ref "C21") (pin "2") (pinfunction "2_2") (pintype "passive"))
      (node (ref "C22") (pin "2") (pinfunction "2_2") (pintype "passive"))
      (node (ref "C23") (pin "2") (pinfunction "2_2") (pintype "passive"))
      (node (ref "C24") (pin "2") (pinfunction "2_2") (pintype "passive"))
      (node (ref "C25") (pin "2") (pinfunction "2_2") (pintype "passive"))
      (node (ref "C26") (pin "2") (pinfunction "2_2") (pintype "passive"))
      (node (ref "C27") (pin "2") (pinfunction "2_2") (pintype "passive"))
      (node (ref "C28") (pin "2") (pinfunction "2_2") (pintype "passive"))
      (node (ref "C29") (pin "2") (pinfunction "2_2") (pintype "passive"))
      (node (ref "C3") (pin "2") (pinfunction "2_2") (pintype "passive"))
      (node (ref "C30") (pin "2") (pinfunction "2_2") (pintype "passive"))
      (node (ref "C31") (pin "2") (pinfunction "2_2") (pintype "passive"))
      (node (ref "C32") (pin "2") (pinfunction "2_2") (pintype "passive"))
      (node (ref "C33") (pin "2") (pinfunction "2_2") (pintype "passive"))
      (node (ref "C34") (pin "2") (pinfunction "2_2") (pintype "passive"))
      (node (ref "C35") (pin "2") (pinfunction "2_2") (pintype "passive"))
      (node (ref "C36") (pin "2") (pinfunction "2_2") (pintype "passive"))
      (node (ref "C37") (pin "2") (pinfunction "2_2") (pintype "passive"))
      (node (ref "C38") (pin "2") (pinfunction "2_2") (pintype "passive"))
      (node (ref "C39") (pin "2") (pinfunction "2_2") (pintype "passive"))
      (node (ref "C4") (pin "2") (pinfunction "2_2") (pintype "passive"))
      (node (ref "C40") (pin "2") (pinfunction "2_2") (pintype "passive"))
      (node (ref "C41") (pin "2") (pinfunction "2_2") (pintype "passive"))
      (node (ref "C42") (pin "1") (pinfunction "1_1") (pintype "passive"))
      (node (ref "C43") (pin "1") (pinfunction "1_1") (pintype "passive"))
      (node (ref "C44") (pin "2") (pinfunction "2_2") (pintype "passive"))
      (node (ref "C45") (pin "2") (pinfunction "2_2") (pintype "passive"))
      (node (ref "C46") (pin "2") (pinfunction "2_2") (pintype "passive"))
      (node (ref "C47") (pin "2") (pinfunction "2_2") (pintype "passive"))
      (node (ref "C48") (pin "2") (pinfunction "2_2") (pintype "passive"))
      (node (ref "C49") (pin "2") (pinfunction "2_2") (pintype "passive"))
      (node (ref "C5") (pin "2") (pinfunction "2_2") (pintype "passive"))
      (node (ref "C50") (pin "2") (pinfunction "2_2") (pintype "passive"))
      (node (ref "C51") (pin "2") (pinfunction "2_2") (pintype "passive"))
      (node (ref "C52") (pin "2") (pinfunction "2_2") (pintype "passive"))
      (node (ref "C53") (pin "2") (pinfunction "2_2") (pintype "passive"))
      (node (ref "C54") (pin "2") (pinfunction "2_2") (pintype "passive"))
      (node (ref "C55") (pin "2") (pinfunction "2_2") (pintype "passive"))
      (node (ref "C56") (pin "2") (pinfunction "2_2") (pintype "passive"))
      (node (ref "C57") (pin "2") (pinfunction "2_2") (pintype "passive"))
      (node (ref "C58") (pin "2") (pinfunction "2_2") (pintype "passive"))
      (node (ref "C59") (pin "2") (pinfunction "2_2") (pintype "passive"))
      (node (ref "C6") (pin "2") (pinfunction "2_2") (pintype "passive"))
      (node (ref "C60") (pin "2") (pinfunction "2_2") (pintype "passive"))
      (node (ref "C61") (pin "2") (pinfunction "2_2") (pintype "passive"))
      (node (ref "C62") (pin "2") (pinfunction "2_2") (pintype "passive"))
      (node (ref "C63") (pin "2") (pinfunction "2_2") (pintype "passive"))
      (node (ref "C64") (pin "2") (pinfunction "2_2") (pintype "passive"))
      (node (ref "C65") (pin "2") (pinfunction "2_2") (pintype "passive"))
      (node (ref "C66") (pin "2") (pinfunction "2_2") (pintype "passive"))
      (node (ref "C67") (pin "2") (pinfunction "2_2") (pintype "passive"))
      (node (ref "C68") (pin "2") (pinfunction "2_2") (pintype "passive"))
      (node (ref "C69") (pin "2") (pinfunction "2_2") (pintype "passive"))
      (node (ref "C7") (pin "2") (pinfunction "2_2") (pintype "passive"))
      (node (ref "C70") (pin "2") (pinfunction "2_2") (pintype "passive"))
      (node (ref "C71") (pin "2") (pinfunction "2_2") (pintype "passive"))
      (node (ref "C72") (pin "2") (pinfunction "2_2") (pintype "passive"))
      (node (ref "C73") (pin "2") (pinfunction "2_2") (pintype "passive"))
      (node (ref "C74") (pin "2") (pinfunction "2_2") (pintype "passive"))
      (node (ref "C75") (pin "2") (pinfunction "2_2") (pintype "passive"))
      (node (ref "C76") (pin "2") (pinfunction "2_2") (pintype "passive"))
      (node (ref "C77") (pin "2") (pinfunction "2_2") (pintype "passive"))
      (node (ref "C78") (pin "2") (pinfunction "2_2") (pintype "passive"))
      (node (ref "C79") (pin "2") (pinfunction "2_2") (pintype "passive"))
      (node (ref "C8") (pin "2") (pinfunction "2_2") (pintype "passive"))
      (node (ref "C80") (pin "2") (pinfunction "2_2") (pintype "passive"))
      (node (ref "C81") (pin "2") (pinfunction "2_2") (pintype "passive"))
      (node (ref "C82") (pin "2") (pinfunction "2_2") (pintype "passive"))
      (node (ref "C83") (pin "2") (pinfunction "2_2") (pintype "passive"))
      (node (ref "C84") (pin "2") (pinfunction "2_2") (pintype "passive"))
      (node (ref "C85") (pin "2") (pinfunction "2_2") (pintype "passive"))
      (node (ref "C86") (pin "2") (pinfunction "2_2") (pintype "passive"))
      (node (ref "C87") (pin "2") (pinfunction "2_2") (pintype "passive"))
      (node (ref "C88") (pin "2") (pinfunction "2_2") (pintype "passive"))
      (node (ref "C89") (pin "2") (pinfunction "2_2") (pintype "passive"))
      (node (ref "C9") (pin "2") (pinfunction "2_2") (pintype "passive"))
      (node (ref "C90") (pin "2") (pinfunction "2_2") (pintype "passive"))
      (node (ref "C91") (pin "2") (pinfunction "2_2") (pintype "passive"))
      (node (ref "C92") (pin "2") (pinfunction "2_2") (pintype "passive"))
      (node (ref "C93") (pin "2") (pinfunction "2_2") (pintype "passive"))
      (node (ref "C94") (pin "2") (pinfunction "2_2") (pintype "passive"))
      (node (ref "C95") (pin "2") (pinfunction "2_2") (pintype "passive"))
      (node (ref "C96") (pin "2") (pinfunction "2_2") (pintype "passive"))
      (node (ref "C97") (pin "2") (pinfunction "2_2") (pintype "passive"))
      (node (ref "C98") (pin "2") (pinfunction "2_2") (pintype "passive"))
      (node (ref "C99") (pin "2") (pinfunction "2_2") (pintype "passive"))
      (node (ref "D226") (pin "2") (pinfunction "C_2") (pintype "passive"))
      (node (ref "J1") (pin "3") (pinfunction "VSS_3") (pintype "power_in"))
      (node (ref "J1") (pin "6") (pinfunction "VSS_6") (pintype "power_in"))
      (node (ref "J1") (pin "G1") (pinfunction "GND_G1") (pintype "power_in"))
      (node (ref "J1") (pin "G2") (pinfunction "GND_G2") (pintype "power_in"))
      (node (ref "J2") (pin "A12_B1") (pinfunction "GND_A12_B1") (pintype "passive"))
      (node (ref "J2") (pin "A1_B12") (pinfunction "GND_A1_B12") (pintype "passive"))
      (node (ref "J2") (pin "SH1") (pinfunction "SHIELD_SH1") (pintype "passive"))
      (node (ref "J2") (pin "SH2") (pinfunction "SHIELD_SH2") (pintype "passive"))
      (node (ref "J2") (pin "SH3") (pinfunction "SHIELD_SH3") (pintype "passive"))
      (node (ref "J2") (pin "SH4") (pinfunction "SHIELD_SH4") (pintype "passive"))
      (node (ref "LED1") (pin "3-GND") (pinfunction "GND_3-GND") (pintype "power_in"))
      (node (ref "LED10") (pin "3-GND") (pinfunction "GND_3-GND") (pintype "power_in"))
      (node (ref "LED11") (pin "3-GND") (pinfunction "GND_3-GND") (pintype "power_in"))
      (node (ref "LED12") (pin "3-GND") (pinfunction "GND_3-GND") (pintype "power_in"))
      (node (ref "LED13") (pin "3-GND") (pinfunction "GND_3-GND") (pintype "power_in"))
      (node (ref "LED14") (pin "3-GND") (pinfunction "GND_3-GND") (pintype "power_in"))
      (node (ref "LED15") (pin "3-GND") (pinfunction "GND_3-GND") (pintype "power_in"))
      (node (ref "LED16") (pin "3-GND") (pinfunction "GND_3-GND") (pintype "power_in"))
      (node (ref "LED17") (pin "3-GND") (pinfunction "GND_3-GND") (pintype "power_in"))
      (node (ref "LED18") (pin "3-GND") (pinfunction "GND_3-GND") (pintype "power_in"))
      (node (ref "LED19") (pin "3-GND") (pinfunction "GND_3-GND") (pintype "power_in"))
      (node (ref "LED2") (pin "3-GND") (pinfunction "GND_3-GND") (pintype "power_in"))
      (node (ref "LED20") (pin "3-GND") (pinfunction "GND_3-GND") (pintype "power_in"))
      (node (ref "LED21") (pin "3-GND") (pinfunction "GND_3-GND") (pintype "power_in"))
      (node (ref "LED22") (pin "3-GND") (pinfunction "GND_3-GND") (pintype "power_in"))
      (node (ref "LED23") (pin "3-GND") (pinfunction "GND_3-GND") (pintype "power_in"))
      (node (ref "LED24") (pin "3-GND") (pinfunction "GND_3-GND") (pintype "power_in"))
      (node (ref "LED25") (pin "3-GND") (pinfunction "GND_3-GND") (pintype "power_in"))
      (node (ref "LED26") (pin "3-GND") (pinfunction "GND_3-GND") (pintype "power_in"))
      (node (ref "LED27") (pin "3-GND") (pinfunction "GND_3-GND") (pintype "power_in"))
      (node (ref "LED28") (pin "3-GND") (pinfunction "GND_3-GND") (pintype "power_in"))
      (node (ref "LED29") (pin "3-GND") (pinfunction "GND_3-GND") (pintype "power_in"))
      (node (ref "LED3") (pin "3-GND") (pinfunction "GND_3-GND") (pintype "power_in"))
      (node (ref "LED30") (pin "3-GND") (pinfunction "GND_3-GND") (pintype "power_in"))
      (node (ref "LED31") (pin "3-GND") (pinfunction "GND_3-GND") (pintype "power_in"))
      (node (ref "LED32") (pin "3-GND") (pinfunction "GND_3-GND") (pintype "power_in"))
      (node (ref "LED33") (pin "3-GND") (pinfunction "GND_3-GND") (pintype "power_in"))
      (node (ref "LED34") (pin "3-GND") (pinfunction "GND_3-GND") (pintype "power_in"))
      (node (ref "LED35") (pin "3-GND") (pinfunction "GND_3-GND") (pintype "power_in"))
      (node (ref "LED36") (pin "3-GND") (pinfunction "GND_3-GND") (pintype "power_in"))
      (node (ref "LED37") (pin "3-GND") (pinfunction "GND_3-GND") (pintype "power_in"))
      (node (ref "LED38") (pin "3-GND") (pinfunction "GND_3-GND") (pintype "power_in"))
      (node (ref "LED39") (pin "3-GND") (pinfunction "GND_3-GND") (pintype "power_in"))
      (node (ref "LED4") (pin "3-GND") (pinfunction "GND_3-GND") (pintype "power_in"))
      (node (ref "LED40") (pin "3-GND") (pinfunction "GND_3-GND") (pintype "power_in"))
      (node (ref "LED41") (pin "3-GND") (pinfunction "GND_3-GND") (pintype "power_in"))
      (node (ref "LED42") (pin "3-GND") (pinfunction "GND_3-GND") (pintype "power_in"))
      (node (ref "LED43") (pin "3-GND") (pinfunction "GND_3-GND") (pintype "power_in"))
      (node (ref "LED44") (pin "3-GND") (pinfunction "GND_3-GND") (pintype "power_in"))
      (node (ref "LED45") (pin "3-GND") (pinfunction "GND_3-GND") (pintype "power_in"))
      (node (ref "LED46") (pin "3-GND") (pinfunction "GND_3-GND") (pintype "power_in"))
      (node (ref "LED47") (pin "3-GND") (pinfunction "GND_3-GND") (pintype "power_in"))
      (node (ref "LED48") (pin "3-GND") (pinfunction "GND_3-GND") (pintype "power_in"))
      (node (ref "LED49") (pin "3-GND") (pinfunction "GND_3-GND") (pintype "power_in"))
      (node (ref "LED5") (pin "3-GND") (pinfunction "GND_3-GND") (pintype "power_in"))
      (node (ref "LED50") (pin "3-GND") (pinfunction "GND_3-GND") (pintype "power_in"))
      (node (ref "LED51") (pin "3-GND") (pinfunction "GND_3-GND") (pintype "power_in"))
      (node (ref "LED52") (pin "3-GND") (pinfunction "GND_3-GND") (pintype "power_in"))
      (node (ref "LED53") (pin "3-GND") (pinfunction "GND_3-GND") (pintype "power_in"))
      (node (ref "LED54") (pin "3-GND") (pinfunction "GND_3-GND") (pintype "power_in"))
      (node (ref "LED55") (pin "3-GND") (pinfunction "GND_3-GND") (pintype "power_in"))
      (node (ref "LED56") (pin "3-GND") (pinfunction "GND_3-GND") (pintype "power_in"))
      (node (ref "LED57") (pin "3-GND") (pinfunction "GND_3-GND") (pintype "power_in"))
      (node (ref "LED58") (pin "3-GND") (pinfunction "GND_3-GND") (pintype "power_in"))
      (node (ref "LED59") (pin "3-GND") (pinfunction "GND_3-GND") (pintype "power_in"))
      (node (ref "LED6") (pin "3-GND") (pinfunction "GND_3-GND") (pintype "power_in"))
      (node (ref "LED60") (pin "3-GND") (pinfunction "GND_3-GND") (pintype "power_in"))
      (node (ref "LED61") (pin "3-GND") (pinfunction "GND_3-GND") (pintype "power_in"))
      (node (ref "LED62") (pin "3-GND") (pinfunction "GND_3-GND") (pintype "power_in"))
      (node (ref "LED63") (pin "3-GND") (pinfunction "GND_3-GND") (pintype "power_in"))
      (node (ref "LED64") (pin "3-GND") (pinfunction "GND_3-GND") (pintype "power_in"))
      (node (ref "LED65") (pin "3-GND") (pinfunction "GND_3-GND") (pintype "power_in"))
      (node (ref "LED66") (pin "3-GND") (pinfunction "GND_3-GND") (pintype "power_in"))
      (node (ref "LED67") (pin "3-GND") (pinfunction "GND_3-GND") (pintype "power_in"))
      (node (ref "LED68") (pin "3-GND") (pinfunction "GND_3-GND") (pintype "power_in"))
      (node (ref "LED69") (pin "3-GND") (pinfunction "GND_3-GND") (pintype "power_in"))
      (node (ref "LED7") (pin "3-GND") (pinfunction "GND_3-GND") (pintype "power_in"))
      (node (ref "LED70") (pin "3-GND") (pinfunction "GND_3-GND") (pintype "power_in"))
      (node (ref "LED71") (pin "3-GND") (pinfunction "GND_3-GND") (pintype "power_in"))
      (node (ref "LED72") (pin "3-GND") (pinfunction "GND_3-GND") (pintype "power_in"))
      (node (ref "LED73") (pin "3-GND") (pinfunction "GND_3-GND") (pintype "power_in"))
      (node (ref "LED74") (pin "3-GND") (pinfunction "GND_3-GND") (pintype "power_in"))
      (node (ref "LED75") (pin "3-GND") (pinfunction "GND_3-GND") (pintype "power_in"))
      (node (ref "LED76") (pin "3-GND") (pinfunction "GND_3-GND") (pintype "power_in"))
      (node (ref "LED77") (pin "3-GND") (pinfunction "GND_3-GND") (pintype "power_in"))
      (node (ref "LED78") (pin "3-GND") (pinfunction "GND_3-GND") (pintype "power_in"))
      (node (ref "LED79") (pin "3-GND") (pinfunction "GND_3-GND") (pintype "power_in"))
      (node (ref "LED8") (pin "3-GND") (pinfunction "GND_3-GND") (pintype "power_in"))
      (node (ref "LED80") (pin "3-GND") (pinfunction "GND_3-GND") (pintype "power_in"))
      (node (ref "LED81") (pin "3-GND") (pinfunction "GND_3-GND") (pintype "power_in"))
      (node (ref "LED82") (pin "3-GND") (pinfunction "GND_3-GND") (pintype "power_in"))
      (node (ref "LED83") (pin "3-GND") (pinfunction "GND_3-GND") (pintype "power_in"))
      (node (ref "LED84") (pin "3-GND") (pinfunction "GND_3-GND") (pintype "power_in"))
      (node (ref "LED85") (pin "3-GND") (pinfunction "GND_3-GND") (pintype "power_in"))
      (node (ref "LED86") (pin "3-GND") (pinfunction "GND_3-GND") (pintype "power_in"))
      (node (ref "LED87") (pin "3-GND") (pinfunction "GND_3-GND") (pintype "power_in"))
      (node (ref "LED88") (pin "3-GND") (pinfunction "GND_3-GND") (pintype "power_in"))
      (node (ref "LED89") (pin "3-GND") (pinfunction "GND_3-GND") (pintype "power_in"))
      (node (ref "LED9") (pin "3-GND") (pinfunction "GND_3-GND") (pintype "power_in"))
      (node (ref "LED90") (pin "3-GND") (pinfunction "GND_3-GND") (pintype "power_in"))
      (node (ref "LED91") (pin "3-GND") (pinfunction "GND_3-GND") (pintype "power_in"))
      (node (ref "LED92") (pin "3-GND") (pinfunction "GND_3-GND") (pintype "power_in"))
      (node (ref "LED93") (pin "3-GND") (pinfunction "GND_3-GND") (pintype "power_in"))
      (node (ref "LED94") (pin "3-GND") (pinfunction "GND_3-GND") (pintype "power_in"))
      (node (ref "LED95") (pin "3-GND") (pinfunction "GND_3-GND") (pintype "power_in"))
      (node (ref "LED96") (pin "3-GND") (pinfunction "GND_3-GND") (pintype "power_in"))
      (node (ref "LED97") (pin "3-GND") (pinfunction "GND_3-GND") (pintype "power_in"))
      (node (ref "LED98") (pin "3-GND") (pinfunction "GND_3-GND") (pintype "power_in"))
      (node (ref "LED99") (pin "3-GND") (pinfunction "GND_3-GND") (pintype "power_in"))
      (node (ref "R18") (pin "2") (pinfunction "2_2") (pintype "passive"))
      (node (ref "R19") (pin "2") (pinfunction "2_2") (pintype "passive"))
      (node (ref "R20") (pin "2") (pinfunction "2_2") (pintype "passive"))
      (node (ref "S0") (pin "3") (pinfunction "P_3") (pintype "passive"))
      (node (ref "S0") (pin "4") (pinfunction "P1_4") (pintype "passive"))
      (node (ref "S1") (pin "3") (pinfunction "P_3") (pintype "passive"))
      (node (ref "S1") (pin "4") (pinfunction "P1_4") (pintype "passive"))
      (node (ref "S2") (pin "3") (pinfunction "P_3") (pintype "passive"))
      (node (ref "S2") (pin "4") (pinfunction "P1_4") (pintype "passive"))
      (node (ref "S3") (pin "3") (pinfunction "P_3") (pintype "passive"))
      (node (ref "S3") (pin "4") (pinfunction "P1_4") (pintype "passive"))
      (node (ref "S4") (pin "3") (pinfunction "P_3") (pintype "passive"))
      (node (ref "S4") (pin "4") (pinfunction "P1_4") (pintype "passive"))
      (node (ref "S5") (pin "3") (pinfunction "P_3") (pintype "passive"))
      (node (ref "S5") (pin "4") (pinfunction "P1_4") (pintype "passive"))
      (node (ref "S6") (pin "3") (pinfunction "P_3") (pintype "passive"))
      (node (ref "S6") (pin "4") (pinfunction "P1_4") (pintype "passive"))
      (node (ref "S7") (pin "3") (pinfunction "P_3") (pintype "passive"))
      (node (ref "S7") (pin "4") (pinfunction "P1_4") (pintype "passive"))
      (node (ref "S8") (pin "3") (pinfunction "P_3") (pintype "passive"))
      (node (ref "S8") (pin "4") (pinfunction "P1_4") (pintype "passive"))
      (node (ref "S9") (pin "3") (pinfunction "P_3") (pintype "passive"))
      (node (ref "S9") (pin "4") (pinfunction "P1_4") (pintype "passive"))
      (node (ref "SR") (pin "3") (pinfunction "P_3") (pintype "passive"))
      (node (ref "SR") (pin "4") (pinfunction "P1_4") (pintype "passive"))
      (node (ref "U$2") (pin "P$1") (pinfunction "P$1_P$1") (pintype "bidirectional"))
      (node (ref "U1") (pin "4") (pinfunction "GND_4") (pintype "power_in"))
      (node (ref "U2") (pin "1") (pinfunction "GND_1") (pintype "power_in"))
      (node (ref "U2") (pin "40") (pinfunction "GND_40") (pintype "power_in"))
      (node (ref "U2") (pin "41_1") (pinfunction "GND_41_1") (pintype "power_in"))
      (node (ref "U2") (pin "41_10") (pinfunction "GND_41_10") (pintype "power_in"))
      (node (ref "U2") (pin "41_11") (pinfunction "GND_41_11") (pintype "power_in"))
      (node (ref "U2") (pin "41_12") (pinfunction "GND_41_12") (pintype "power_in"))
      (node (ref "U2") (pin "41_13") (pinfunction "GND_41_13") (pintype "power_in"))
      (node (ref "U2") (pin "41_14") (pinfunction "GND_41_14") (pintype "power_in"))
      (node (ref "U2") (pin "41_15") (pinfunction "GND_41_15") (pintype "power_in"))
      (node (ref "U2") (pin "41_16") (pinfunction "GND_41_16") (pintype "power_in"))
      (node (ref "U2") (pin "41_17") (pinfunction "GND_41_17") (pintype "power_in"))
      (node (ref "U2") (pin "41_18") (pinfunction "GND_41_18") (pintype "power_in"))
      (node (ref "U2") (pin "41_19") (pinfunction "GND_41_19") (pintype "power_in"))
      (node (ref "U2") (pin "41_2") (pinfunction "GND_41_2") (pintype "power_in"))
      (node (ref "U2") (pin "41_20") (pinfunction "GND_41_20") (pintype "power_in"))
      (node (ref "U2") (pin "41_21") (pinfunction "GND_41_21") (pintype "power_in"))
      (node (ref "U2") (pin "41_3") (pinfunction "GND_41_3") (pintype "power_in"))
      (node (ref "U2") (pin "41_4") (pinfunction "GND_41_4") (pintype "power_in"))
      (node (ref "U2") (pin "41_5") (pinfunction "GND_41_5") (pintype "power_in"))
      (node (ref "U2") (pin "41_6") (pinfunction "GND_41_6") (pintype "power_in"))
      (node (ref "U2") (pin "41_7") (pinfunction "GND_41_7") (pintype "power_in"))
      (node (ref "U2") (pin "41_8") (pinfunction "GND_41_8") (pintype "power_in"))
      (node (ref "U2") (pin "41_9") (pinfunction "GND_41_9") (pintype "power_in"))
      (node (ref "VR1") (pin "2") (pinfunction "COMMON_2_2") (pintype "power_in"))
      (node (ref "VR1") (pin "4") (pinfunction "COMMON_4_4") (pintype "power_in"))
    )
    (net (code "141") (name "unconnected-(J1-DAT1-Pad8)") (class "Default")
      (node (ref "J1") (pin "8") (pinfunction "DAT1_8") (pintype "bidirectional"))
    )
    (net (code "142") (name "unconnected-(J1-DAT2-Pad9)") (class "Default")
      (node (ref "J1") (pin "9") (pinfunction "DAT2_9") (pintype "bidirectional"))
    )
    (net (code "143") (name "unconnected-(J1-PadCD)") (class "Default")
      (node (ref "J1") (pin "CD") (pinfunction "CD_CD") (pintype "input"))
    )
    (net (code "144") (name "unconnected-(J1-PadWP)") (class "Default")
      (node (ref "J1") (pin "WP") (pinfunction "WP_WP") (pintype "input"))
    )
    (net (code "145") (name "unconnected-(J2-CC1-PadA5)") (class "Default")
      (node (ref "J2") (pin "A5") (pinfunction "CC1_A5") (pintype "passive"))
    )
    (net (code "146") (name "unconnected-(J2-CC2-PadB5)") (class "Default")
      (node (ref "J2") (pin "B5") (pinfunction "CC2_B5") (pintype "passive"))
    )
    (net (code "147") (name "unconnected-(J2-SBU1-PadA8)") (class "Default")
      (node (ref "J2") (pin "A8") (pinfunction "SBU1_A8") (pintype "passive"))
    )
    (net (code "148") (name "unconnected-(J2-SBU2-PadB8)") (class "Default")
      (node (ref "J2") (pin "B8") (pinfunction "SBU2_B8") (pintype "passive"))
    )
    (net (code "149") (name "unconnected-(LED99-DO-Pad2-DOUT)") (class "Default")
      (node (ref "LED99") (pin "2-DOUT") (pinfunction "DO_2-DOUT") (pintype "output"))
    )
    (net (code "150") (name "unconnected-(U2-IO3-Pad15)") (class "Default")
      (node (ref "U2") (pin "15") (pinfunction "IO3_15") (pintype "bidirectional"))
    )
    (net (code "151") (name "unconnected-(U2-IO45-Pad26)") (class "Default")
      (node (ref "U2") (pin "26") (pinfunction "IO45_26") (pintype "bidirectional"))
    )
    (net (code "152") (name "unconnected-(U2-IO46-Pad16)") (class "Default")
      (node (ref "U2") (pin "16") (pinfunction "IO46_16") (pintype "bidirectional"))
    )
    (net (code "153") (name "unconnected-(U2-IO47-Pad24)") (class "Default")
      (node (ref "U2") (pin "24") (pinfunction "IO47_24") (pintype "bidirectional"))
    )
    (net (code "154") (name "unconnected-(U2-IO48-Pad25)") (class "Default")
      (node (ref "U2") (pin "25") (pinfunction "IO48_25") (pintype "bidirectional"))
    )
    (net (code "155") (name "unconnected-(U2-RXD0-Pad36)") (class "Default")
      (node (ref "U2") (pin "36") (pinfunction "RXD0_36") (pintype "bidirectional"))
    )
    (net (code "156") (name "unconnected-(U2-TXD0-Pad37)") (class "Default")
      (node (ref "U2") (pin "37") (pinfunction "TXD0_37") (pintype "bidirectional"))
    )
  )
)
